# Decoder.net
KiCad netlist of a schematic drawn in EAGLE
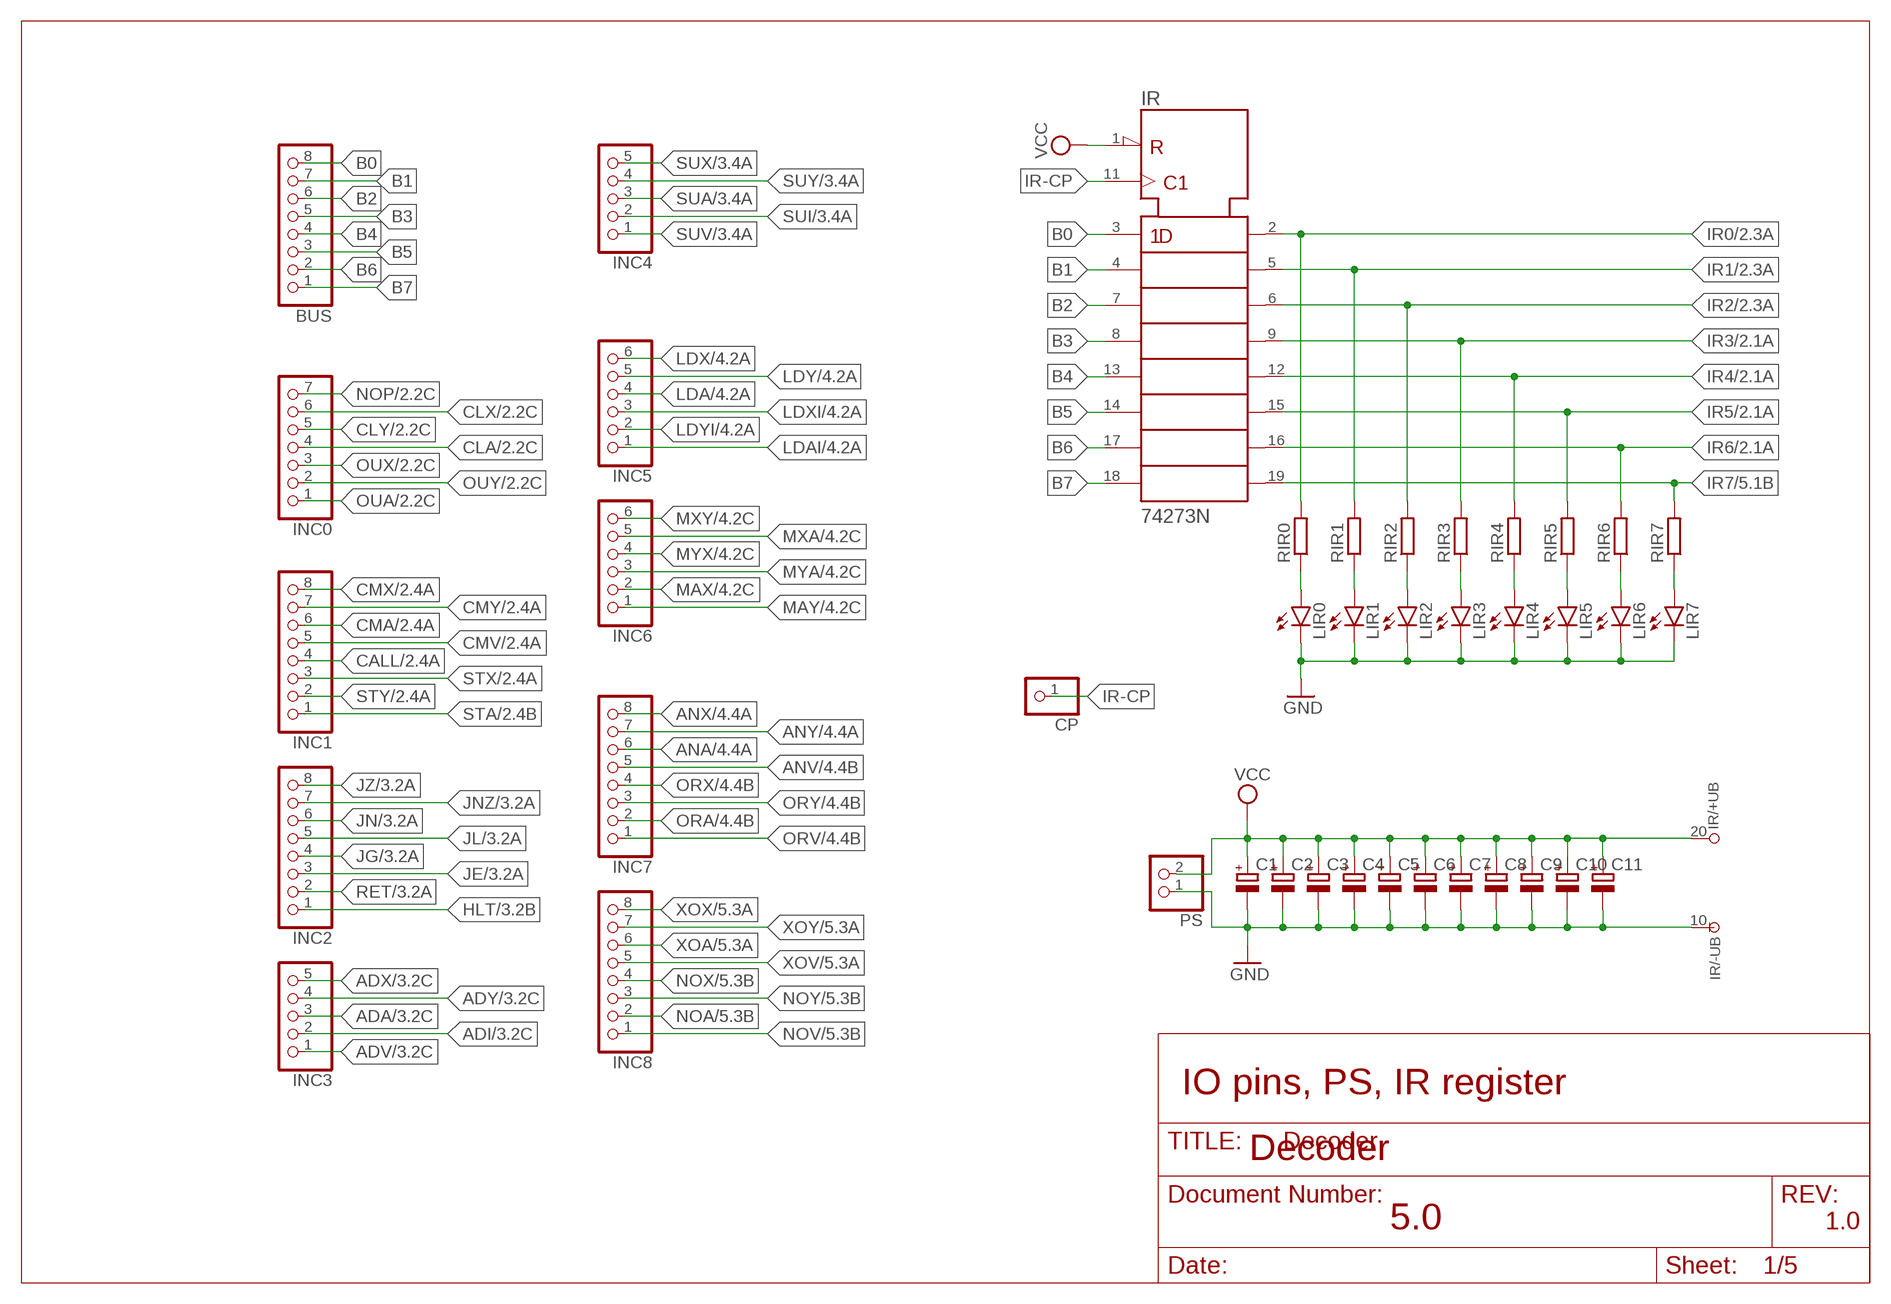
[diagram p0: schematic, sheet 1]
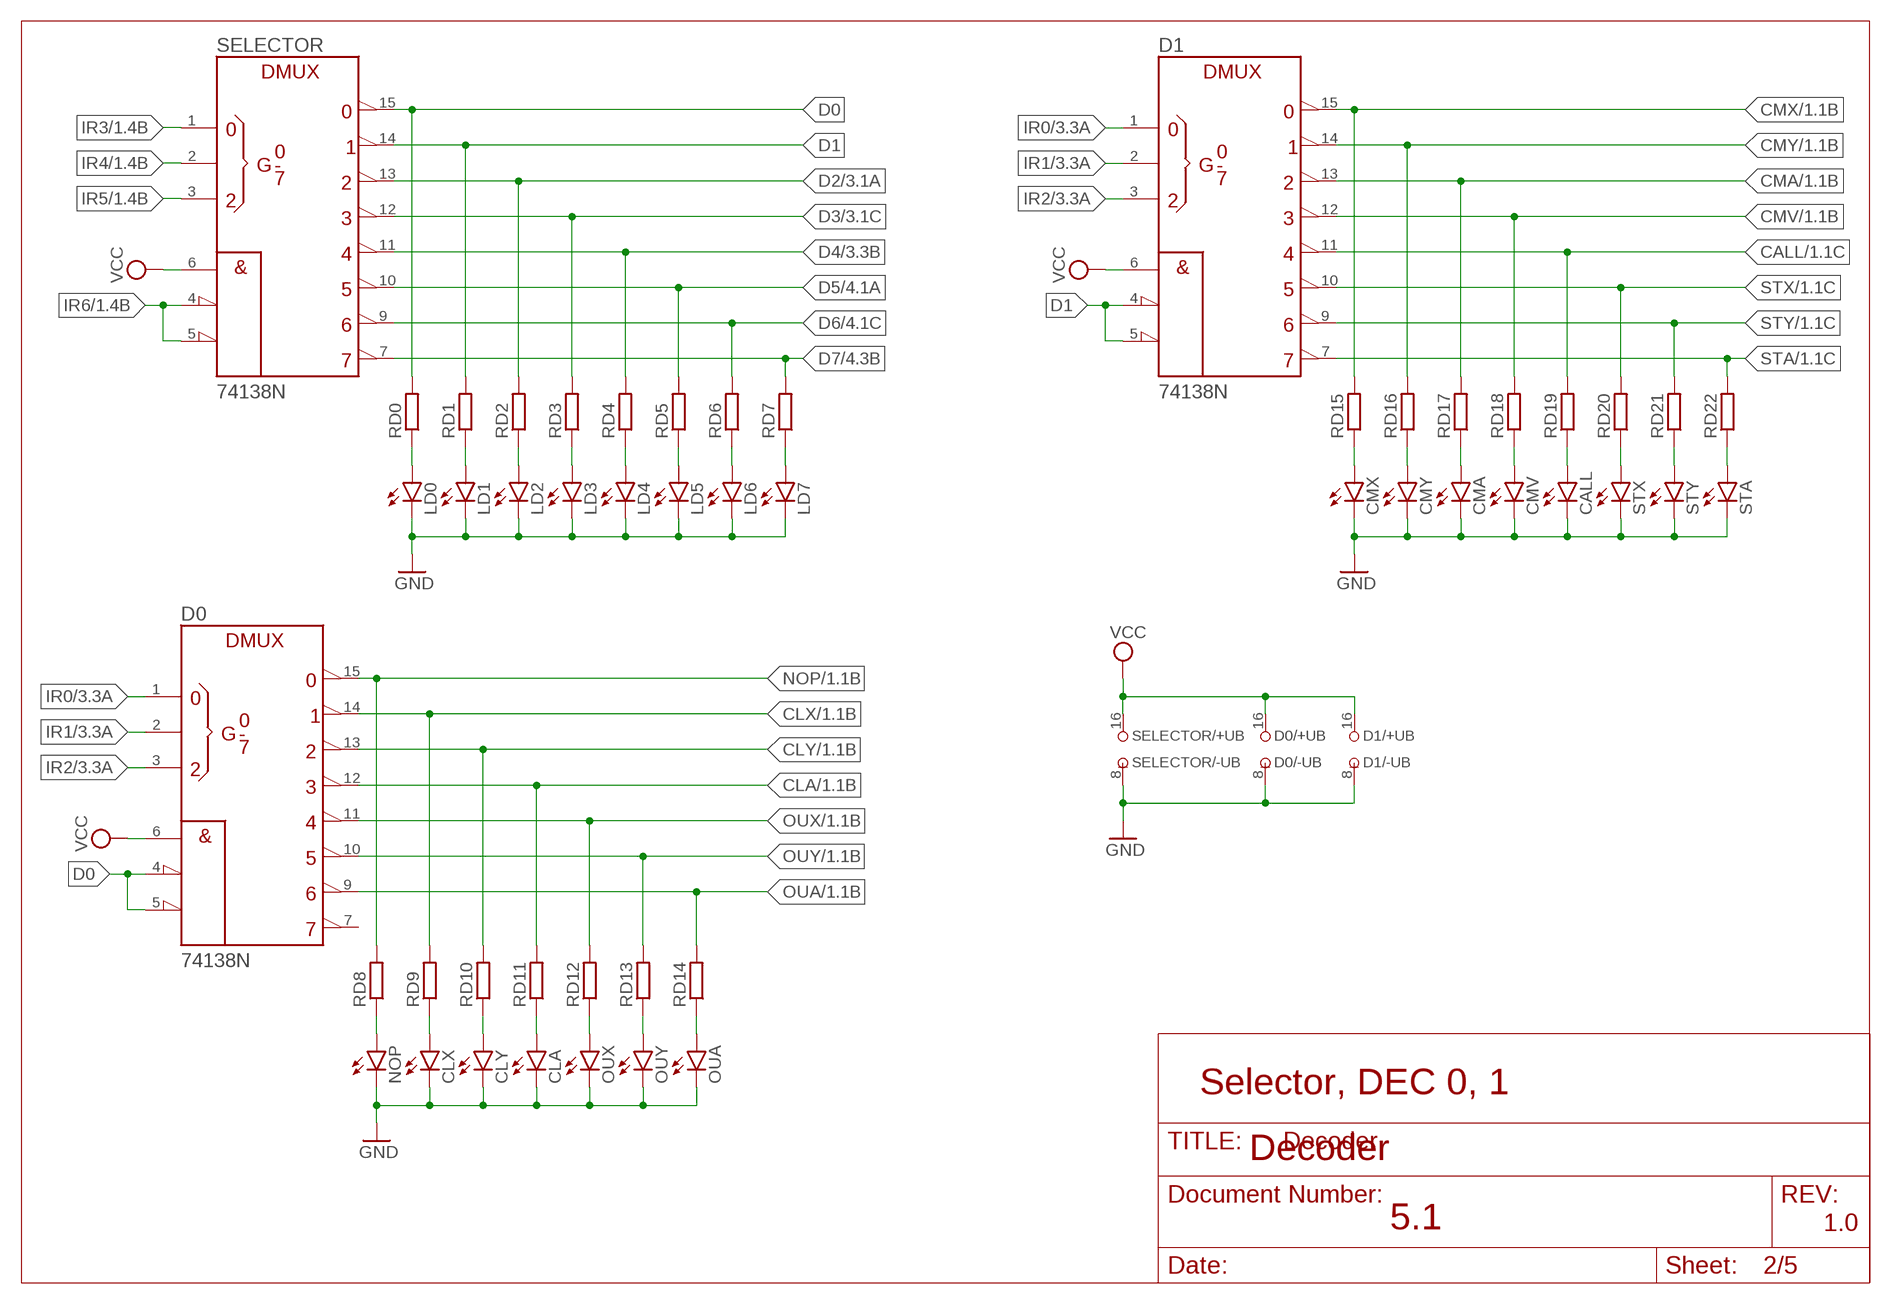
[diagram p1: schematic, sheet 2]
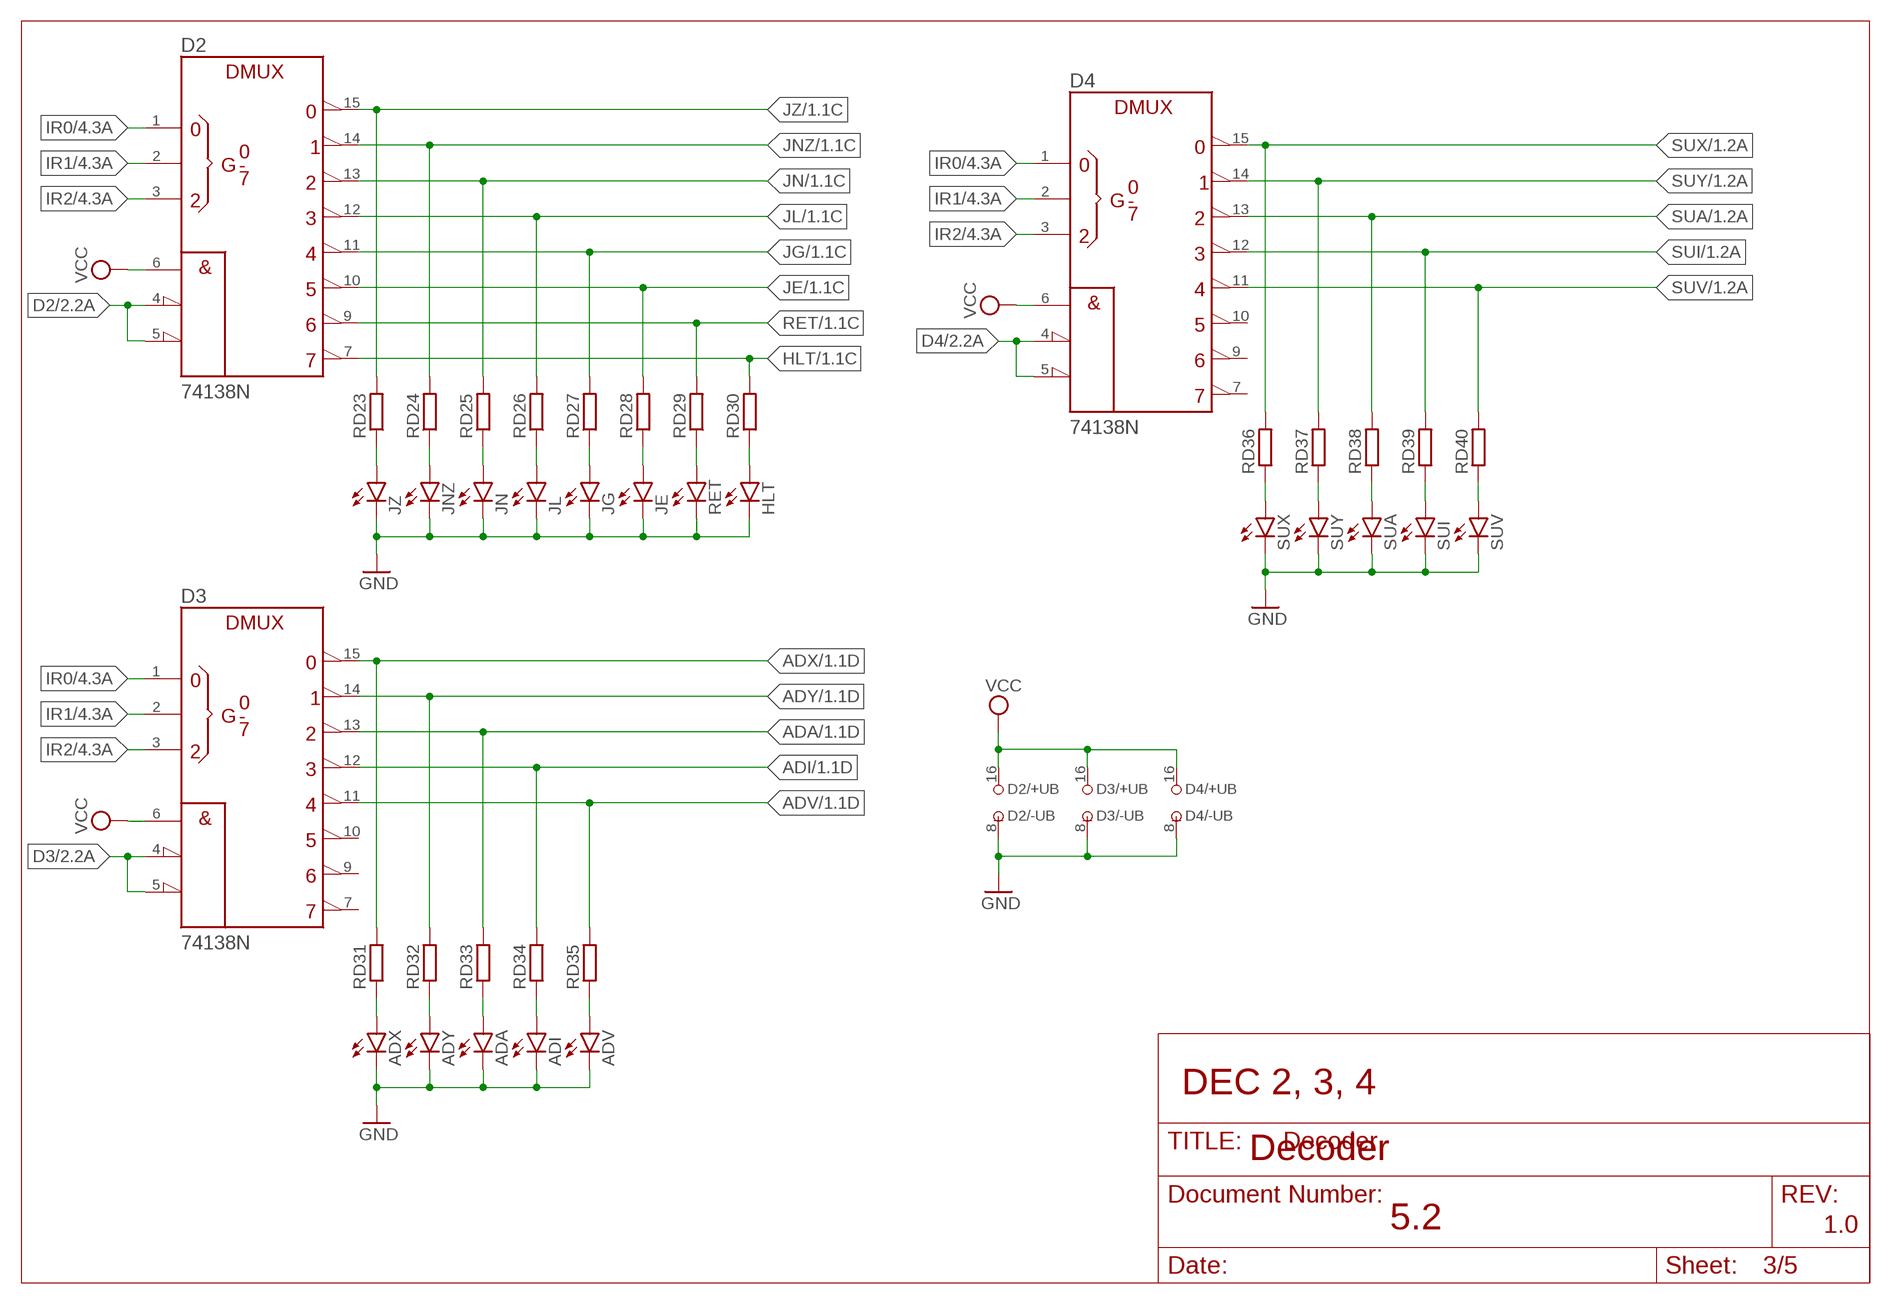
[diagram p2: schematic, sheet 3]
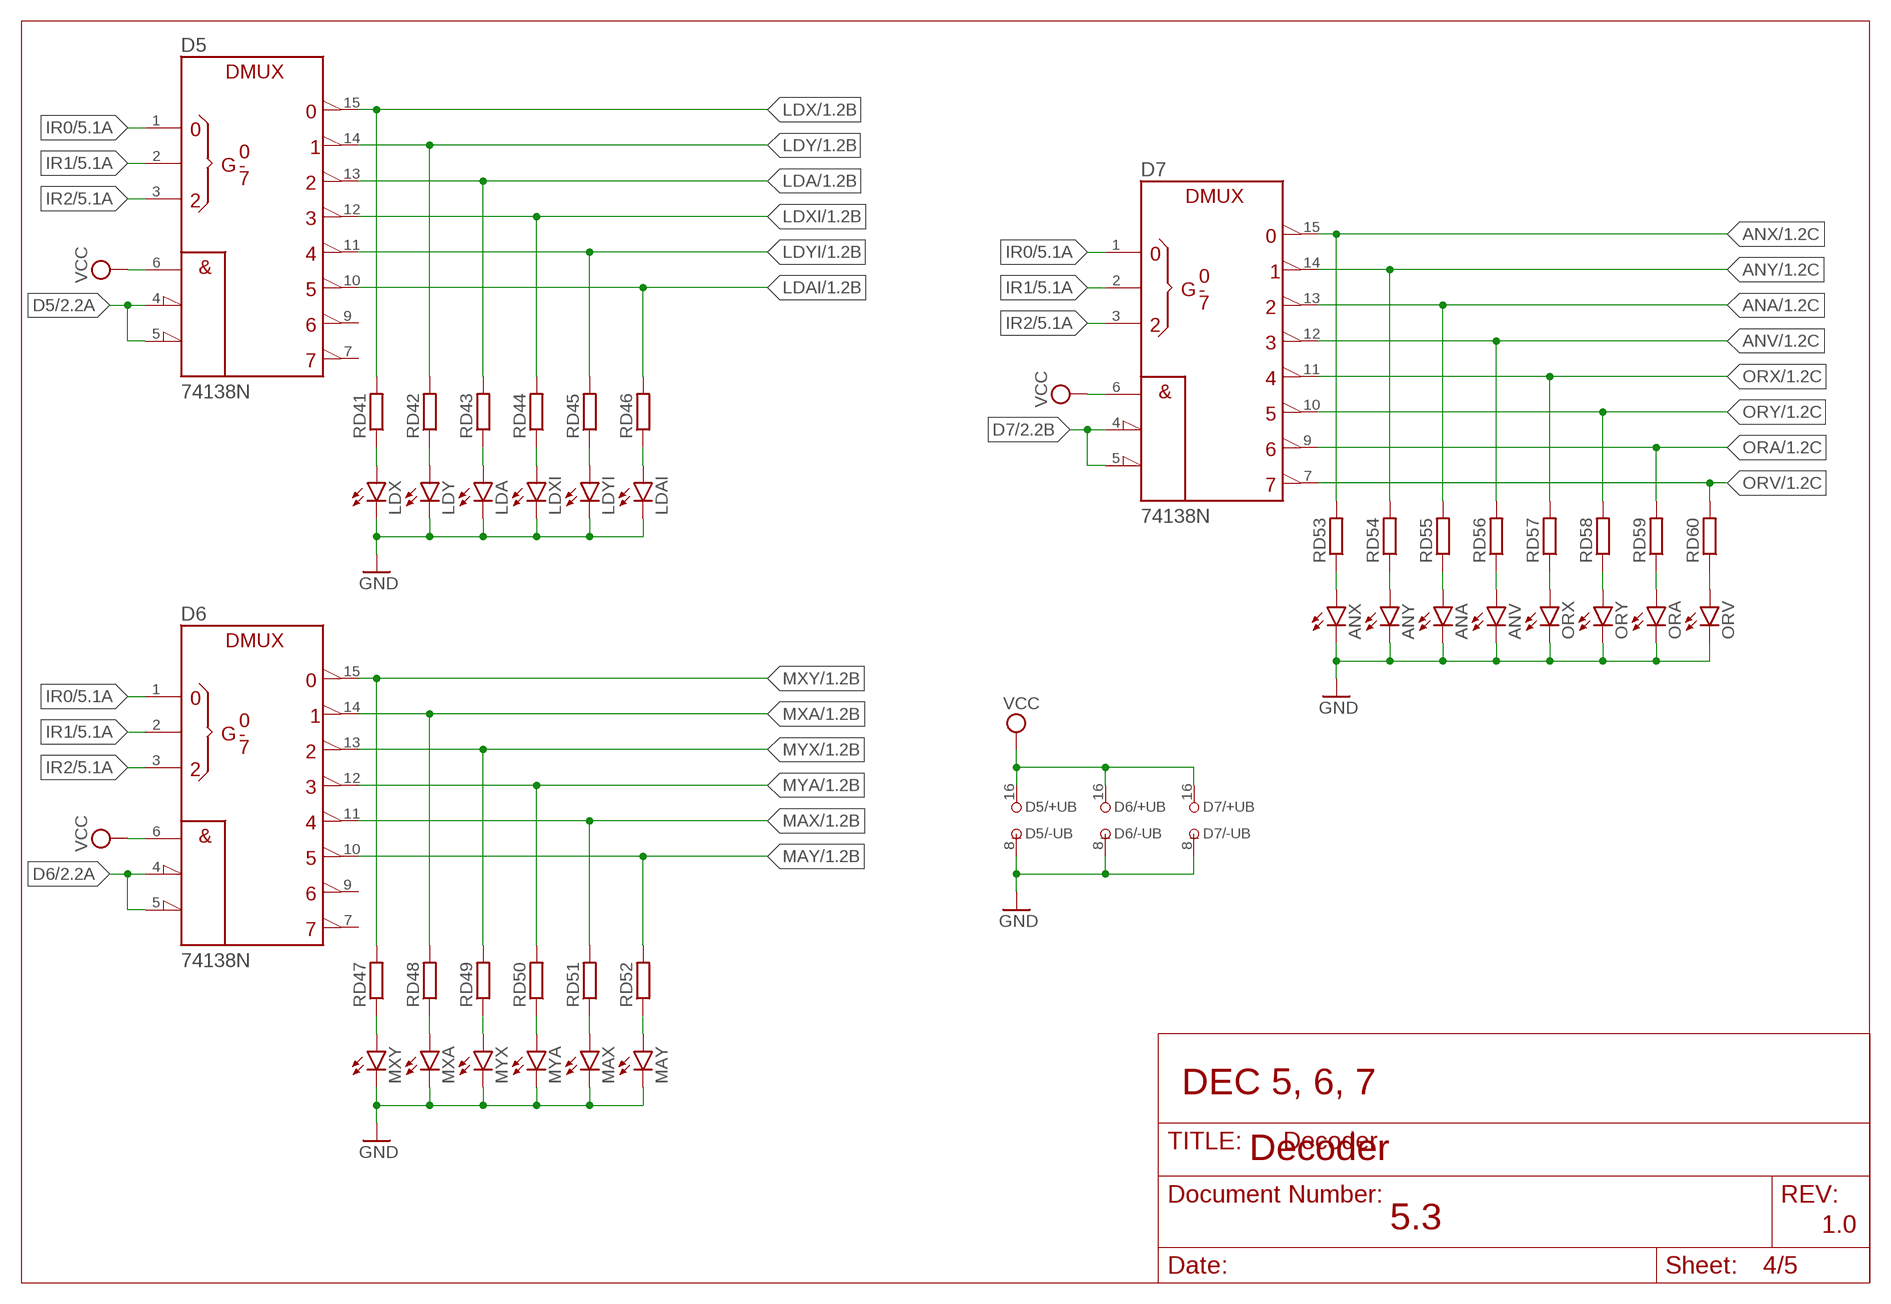
[diagram p3: schematic, sheet 4]
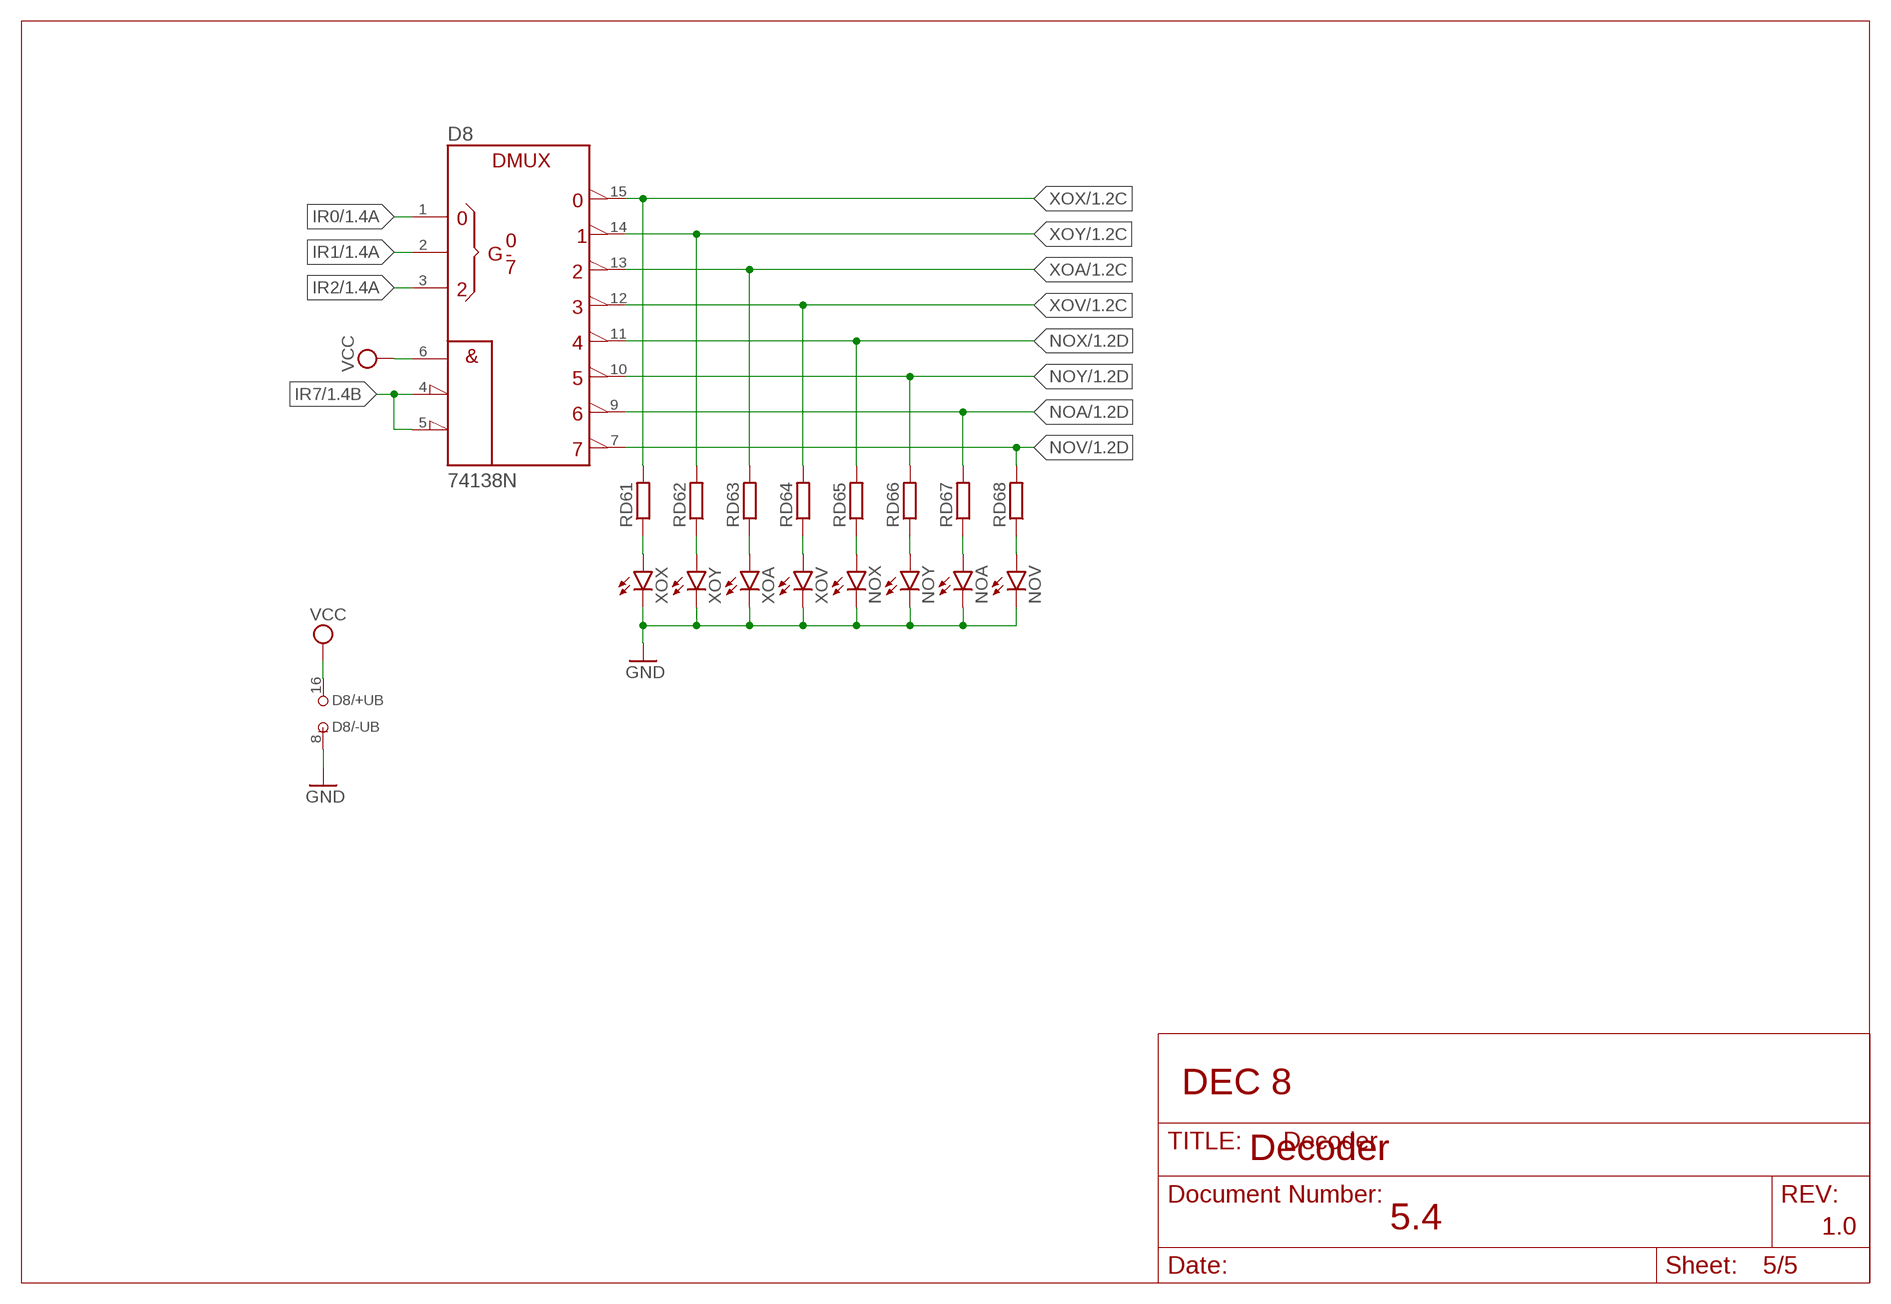
[diagram p4: schematic, sheet 5]

(export (version "E")
  (design (tool "Eeschema 10.0.6"))
  (components
    (comp (ref "CALL")
      (value "LED5MM")
      (footprint "eagle-import:LED5MM")
      (libsource (lib "eagle-import") (part "LED5MM"))
    )
    (comp (ref "CLA")
      (value "LED5MM")
      (footprint "eagle-import:LED5MM")
      (libsource (lib "eagle-import") (part "LED5MM"))
    )
    (comp (ref "CLX")
      (value "LED5MM")
      (footprint "eagle-import:LED5MM")
      (libsource (lib "eagle-import") (part "LED5MM"))
    )
    (comp (ref "CLY")
      (value "LED5MM")
      (footprint "eagle-import:LED5MM")
      (libsource (lib "eagle-import") (part "LED5MM"))
    )
    (comp (ref "CMA")
      (value "LED5MM")
      (footprint "eagle-import:LED5MM")
      (libsource (lib "eagle-import") (part "LED5MM"))
    )
    (comp (ref "CMV")
      (value "LED5MM")
      (footprint "eagle-import:LED5MM")
      (libsource (lib "eagle-import") (part "LED5MM"))
    )
    (comp (ref "CMX")
      (value "LED5MM")
      (footprint "eagle-import:LED5MM")
      (libsource (lib "eagle-import") (part "LED5MM"))
    )
    (comp (ref "CMY")
      (value "LED5MM")
      (footprint "eagle-import:LED5MM")
      (libsource (lib "eagle-import") (part "LED5MM"))
    )
    (comp (ref "D0")
      (value "74138N")
      (footprint "eagle-import:DIL16")
      (libsource (lib "eagle-import") (part "74138N"))
    )
    (comp (ref "D1")
      (value "74138N")
      (footprint "eagle-import:DIL16")
      (libsource (lib "eagle-import") (part "74138N"))
    )
    (comp (ref "LD0")
      (value "LED5MM")
      (footprint "eagle-import:LED5MM")
      (libsource (lib "eagle-import") (part "LED5MM"))
    )
    (comp (ref "LD1")
      (value "LED5MM")
      (footprint "eagle-import:LED5MM")
      (libsource (lib "eagle-import") (part "LED5MM"))
    )
    (comp (ref "LD2")
      (value "LED5MM")
      (footprint "eagle-import:LED5MM")
      (libsource (lib "eagle-import") (part "LED5MM"))
    )
    (comp (ref "LD3")
      (value "LED5MM")
      (footprint "eagle-import:LED5MM")
      (libsource (lib "eagle-import") (part "LED5MM"))
    )
    (comp (ref "LD4")
      (value "LED5MM")
      (footprint "eagle-import:LED5MM")
      (libsource (lib "eagle-import") (part "LED5MM"))
    )
    (comp (ref "LD5")
      (value "LED5MM")
      (footprint "eagle-import:LED5MM")
      (libsource (lib "eagle-import") (part "LED5MM"))
    )
    (comp (ref "LD6")
      (value "LED5MM")
      (footprint "eagle-import:LED5MM")
      (libsource (lib "eagle-import") (part "LED5MM"))
    )
    (comp (ref "LD7")
      (value "LED5MM")
      (footprint "eagle-import:LED5MM")
      (libsource (lib "eagle-import") (part "LED5MM"))
    )
    (comp (ref "NOP")
      (value "LED5MM")
      (footprint "eagle-import:LED5MM")
      (libsource (lib "eagle-import") (part "LED5MM"))
    )
    (comp (ref "OUA")
      (value "LED5MM")
      (footprint "eagle-import:LED5MM")
      (libsource (lib "eagle-import") (part "LED5MM"))
    )
    (comp (ref "OUX")
      (value "LED5MM")
      (footprint "eagle-import:LED5MM")
      (libsource (lib "eagle-import") (part "LED5MM"))
    )
    (comp (ref "OUY")
      (value "LED5MM")
      (footprint "eagle-import:LED5MM")
      (libsource (lib "eagle-import") (part "LED5MM"))
    )
    (comp (ref "RD0")
      (value "R-EU_0204/7")
      (footprint "eagle-import:0204_7")
      (libsource (lib "eagle-import") (part "R-EU_0204/7"))
    )
    (comp (ref "RD1")
      (value "R-EU_0204/7")
      (footprint "eagle-import:0204_7")
      (libsource (lib "eagle-import") (part "R-EU_0204/7"))
    )
    (comp (ref "RD2")
      (value "R-EU_0204/7")
      (footprint "eagle-import:0204_7")
      (libsource (lib "eagle-import") (part "R-EU_0204/7"))
    )
    (comp (ref "RD3")
      (value "R-EU_0204/7")
      (footprint "eagle-import:0204_7")
      (libsource (lib "eagle-import") (part "R-EU_0204/7"))
    )
    (comp (ref "RD4")
      (value "R-EU_0204/7")
      (footprint "eagle-import:0204_7")
      (libsource (lib "eagle-import") (part "R-EU_0204/7"))
    )
    (comp (ref "RD5")
      (value "R-EU_0204/7")
      (footprint "eagle-import:0204_7")
      (libsource (lib "eagle-import") (part "R-EU_0204/7"))
    )
    (comp (ref "RD6")
      (value "R-EU_0204/7")
      (footprint "eagle-import:0204_7")
      (libsource (lib "eagle-import") (part "R-EU_0204/7"))
    )
    (comp (ref "RD7")
      (value "R-EU_0204/7")
      (footprint "eagle-import:0204_7")
      (libsource (lib "eagle-import") (part "R-EU_0204/7"))
    )
    (comp (ref "RD8")
      (value "R-EU_0204/7")
      (footprint "eagle-import:0204_7")
      (libsource (lib "eagle-import") (part "R-EU_0204/7"))
    )
    (comp (ref "RD9")
      (value "R-EU_0204/7")
      (footprint "eagle-import:0204_7")
      (libsource (lib "eagle-import") (part "R-EU_0204/7"))
    )
    (comp (ref "RD10")
      (value "R-EU_0204/7")
      (footprint "eagle-import:0204_7")
      (libsource (lib "eagle-import") (part "R-EU_0204/7"))
    )
    (comp (ref "RD11")
      (value "R-EU_0204/7")
      (footprint "eagle-import:0204_7")
      (libsource (lib "eagle-import") (part "R-EU_0204/7"))
    )
    (comp (ref "RD12")
      (value "R-EU_0204/7")
      (footprint "eagle-import:0204_7")
      (libsource (lib "eagle-import") (part "R-EU_0204/7"))
    )
    (comp (ref "RD13")
      (value "R-EU_0204/7")
      (footprint "eagle-import:0204_7")
      (libsource (lib "eagle-import") (part "R-EU_0204/7"))
    )
    (comp (ref "RD14")
      (value "R-EU_0204/7")
      (footprint "eagle-import:0204_7")
      (libsource (lib "eagle-import") (part "R-EU_0204/7"))
    )
    (comp (ref "RD15")
      (value "R-EU_0204/7")
      (footprint "eagle-import:0204_7")
      (libsource (lib "eagle-import") (part "R-EU_0204/7"))
    )
    (comp (ref "RD16")
      (value "R-EU_0204/7")
      (footprint "eagle-import:0204_7")
      (libsource (lib "eagle-import") (part "R-EU_0204/7"))
    )
    (comp (ref "RD17")
      (value "R-EU_0204/7")
      (footprint "eagle-import:0204_7")
      (libsource (lib "eagle-import") (part "R-EU_0204/7"))
    )
    (comp (ref "RD18")
      (value "R-EU_0204/7")
      (footprint "eagle-import:0204_7")
      (libsource (lib "eagle-import") (part "R-EU_0204/7"))
    )
    (comp (ref "RD19")
      (value "R-EU_0204/7")
      (footprint "eagle-import:0204_7")
      (libsource (lib "eagle-import") (part "R-EU_0204/7"))
    )
    (comp (ref "RD20")
      (value "R-EU_0204/7")
      (footprint "eagle-import:0204_7")
      (libsource (lib "eagle-import") (part "R-EU_0204/7"))
    )
    (comp (ref "RD21")
      (value "R-EU_0204/7")
      (footprint "eagle-import:0204_7")
      (libsource (lib "eagle-import") (part "R-EU_0204/7"))
    )
    (comp (ref "RD22")
      (value "R-EU_0204/7")
      (footprint "eagle-import:0204_7")
      (libsource (lib "eagle-import") (part "R-EU_0204/7"))
    )
    (comp (ref "SELECTOR")
      (value "74138N")
      (footprint "eagle-import:DIL16")
      (libsource (lib "eagle-import") (part "74138N"))
    )
    (comp (ref "STA")
      (value "LED5MM")
      (footprint "eagle-import:LED5MM")
      (libsource (lib "eagle-import") (part "LED5MM"))
    )
    (comp (ref "STX")
      (value "LED5MM")
      (footprint "eagle-import:LED5MM")
      (libsource (lib "eagle-import") (part "LED5MM"))
    )
    (comp (ref "STY")
      (value "LED5MM")
      (footprint "eagle-import:LED5MM")
      (libsource (lib "eagle-import") (part "LED5MM"))
    )
    (comp (ref "ANA")
      (value "LED5MM")
      (footprint "eagle-import:LED5MM")
      (libsource (lib "eagle-import") (part "LED5MM"))
    )
    (comp (ref "ANV")
      (value "LED5MM")
      (footprint "eagle-import:LED5MM")
      (libsource (lib "eagle-import") (part "LED5MM"))
    )
    (comp (ref "ANX")
      (value "LED5MM")
      (footprint "eagle-import:LED5MM")
      (libsource (lib "eagle-import") (part "LED5MM"))
    )
    (comp (ref "ANY")
      (value "LED5MM")
      (footprint "eagle-import:LED5MM")
      (libsource (lib "eagle-import") (part "LED5MM"))
    )
    (comp (ref "D5")
      (value "74138N")
      (footprint "eagle-import:DIL16")
      (libsource (lib "eagle-import") (part "74138N"))
    )
    (comp (ref "D6")
      (value "74138N")
      (footprint "eagle-import:DIL16")
      (libsource (lib "eagle-import") (part "74138N"))
    )
    (comp (ref "D7")
      (value "74138N")
      (footprint "eagle-import:DIL16")
      (libsource (lib "eagle-import") (part "74138N"))
    )
    (comp (ref "LDA")
      (value "LED5MM")
      (footprint "eagle-import:LED5MM")
      (libsource (lib "eagle-import") (part "LED5MM"))
    )
    (comp (ref "LDAI")
      (value "LED5MM")
      (footprint "eagle-import:LED5MM")
      (libsource (lib "eagle-import") (part "LED5MM"))
    )
    (comp (ref "LDX")
      (value "LED5MM")
      (footprint "eagle-import:LED5MM")
      (libsource (lib "eagle-import") (part "LED5MM"))
    )
    (comp (ref "LDXI")
      (value "LED5MM")
      (footprint "eagle-import:LED5MM")
      (libsource (lib "eagle-import") (part "LED5MM"))
    )
    (comp (ref "LDY")
      (value "LED5MM")
      (footprint "eagle-import:LED5MM")
      (libsource (lib "eagle-import") (part "LED5MM"))
    )
    (comp (ref "LDYI")
      (value "LED5MM")
      (footprint "eagle-import:LED5MM")
      (libsource (lib "eagle-import") (part "LED5MM"))
    )
    (comp (ref "MAX")
      (value "LED5MM")
      (footprint "eagle-import:LED5MM")
      (libsource (lib "eagle-import") (part "LED5MM"))
    )
    (comp (ref "MAY")
      (value "LED5MM")
      (footprint "eagle-import:LED5MM")
      (libsource (lib "eagle-import") (part "LED5MM"))
    )
    (comp (ref "MXA")
      (value "LED5MM")
      (footprint "eagle-import:LED5MM")
      (libsource (lib "eagle-import") (part "LED5MM"))
    )
    (comp (ref "MXY")
      (value "LED5MM")
      (footprint "eagle-import:LED5MM")
      (libsource (lib "eagle-import") (part "LED5MM"))
    )
    (comp (ref "MYA")
      (value "LED5MM")
      (footprint "eagle-import:LED5MM")
      (libsource (lib "eagle-import") (part "LED5MM"))
    )
    (comp (ref "MYX")
      (value "LED5MM")
      (footprint "eagle-import:LED5MM")
      (libsource (lib "eagle-import") (part "LED5MM"))
    )
    (comp (ref "ORA")
      (value "LED5MM")
      (footprint "eagle-import:LED5MM")
      (libsource (lib "eagle-import") (part "LED5MM"))
    )
    (comp (ref "ORV")
      (value "LED5MM")
      (footprint "eagle-import:LED5MM")
      (libsource (lib "eagle-import") (part "LED5MM"))
    )
    (comp (ref "ORX")
      (value "LED5MM")
      (footprint "eagle-import:LED5MM")
      (libsource (lib "eagle-import") (part "LED5MM"))
    )
    (comp (ref "ORY")
      (value "LED5MM")
      (footprint "eagle-import:LED5MM")
      (libsource (lib "eagle-import") (part "LED5MM"))
    )
    (comp (ref "RD41")
      (value "R-EU_0204/7")
      (footprint "eagle-import:0204_7")
      (libsource (lib "eagle-import") (part "R-EU_0204/7"))
    )
    (comp (ref "RD42")
      (value "R-EU_0204/7")
      (footprint "eagle-import:0204_7")
      (libsource (lib "eagle-import") (part "R-EU_0204/7"))
    )
    (comp (ref "RD43")
      (value "R-EU_0204/7")
      (footprint "eagle-import:0204_7")
      (libsource (lib "eagle-import") (part "R-EU_0204/7"))
    )
    (comp (ref "RD44")
      (value "R-EU_0204/7")
      (footprint "eagle-import:0204_7")
      (libsource (lib "eagle-import") (part "R-EU_0204/7"))
    )
    (comp (ref "RD45")
      (value "R-EU_0204/7")
      (footprint "eagle-import:0204_7")
      (libsource (lib "eagle-import") (part "R-EU_0204/7"))
    )
    (comp (ref "RD46")
      (value "R-EU_0204/7")
      (footprint "eagle-import:0204_7")
      (libsource (lib "eagle-import") (part "R-EU_0204/7"))
    )
    (comp (ref "RD47")
      (value "R-EU_0204/7")
      (footprint "eagle-import:0204_7")
      (libsource (lib "eagle-import") (part "R-EU_0204/7"))
    )
    (comp (ref "RD48")
      (value "R-EU_0204/7")
      (footprint "eagle-import:0204_7")
      (libsource (lib "eagle-import") (part "R-EU_0204/7"))
    )
    (comp (ref "RD49")
      (value "R-EU_0204/7")
      (footprint "eagle-import:0204_7")
      (libsource (lib "eagle-import") (part "R-EU_0204/7"))
    )
    (comp (ref "RD50")
      (value "R-EU_0204/7")
      (footprint "eagle-import:0204_7")
      (libsource (lib "eagle-import") (part "R-EU_0204/7"))
    )
    (comp (ref "RD51")
      (value "R-EU_0204/7")
      (footprint "eagle-import:0204_7")
      (libsource (lib "eagle-import") (part "R-EU_0204/7"))
    )
    (comp (ref "RD52")
      (value "R-EU_0204/7")
      (footprint "eagle-import:0204_7")
      (libsource (lib "eagle-import") (part "R-EU_0204/7"))
    )
    (comp (ref "RD53")
      (value "R-EU_0204/7")
      (footprint "eagle-import:0204_7")
      (libsource (lib "eagle-import") (part "R-EU_0204/7"))
    )
    (comp (ref "RD54")
      (value "R-EU_0204/7")
      (footprint "eagle-import:0204_7")
      (libsource (lib "eagle-import") (part "R-EU_0204/7"))
    )
    (comp (ref "RD55")
      (value "R-EU_0204/7")
      (footprint "eagle-import:0204_7")
      (libsource (lib "eagle-import") (part "R-EU_0204/7"))
    )
    (comp (ref "RD56")
      (value "R-EU_0204/7")
      (footprint "eagle-import:0204_7")
      (libsource (lib "eagle-import") (part "R-EU_0204/7"))
    )
    (comp (ref "RD57")
      (value "R-EU_0204/7")
      (footprint "eagle-import:0204_7")
      (libsource (lib "eagle-import") (part "R-EU_0204/7"))
    )
    (comp (ref "RD58")
      (value "R-EU_0204/7")
      (footprint "eagle-import:0204_7")
      (libsource (lib "eagle-import") (part "R-EU_0204/7"))
    )
    (comp (ref "RD59")
      (value "R-EU_0204/7")
      (footprint "eagle-import:0204_7")
      (libsource (lib "eagle-import") (part "R-EU_0204/7"))
    )
    (comp (ref "RD60")
      (value "R-EU_0204/7")
      (footprint "eagle-import:0204_7")
      (libsource (lib "eagle-import") (part "R-EU_0204/7"))
    )
    (comp (ref "ADA")
      (value "LED5MM")
      (footprint "eagle-import:LED5MM")
      (libsource (lib "eagle-import") (part "LED5MM"))
    )
    (comp (ref "ADI")
      (value "LED5MM")
      (footprint "eagle-import:LED5MM")
      (libsource (lib "eagle-import") (part "LED5MM"))
    )
    (comp (ref "ADV")
      (value "LED5MM")
      (footprint "eagle-import:LED5MM")
      (libsource (lib "eagle-import") (part "LED5MM"))
    )
    (comp (ref "ADX")
      (value "LED5MM")
      (footprint "eagle-import:LED5MM")
      (libsource (lib "eagle-import") (part "LED5MM"))
    )
    (comp (ref "ADY")
      (value "LED5MM")
      (footprint "eagle-import:LED5MM")
      (libsource (lib "eagle-import") (part "LED5MM"))
    )
    (comp (ref "D2")
      (value "74138N")
      (footprint "eagle-import:DIL16")
      (libsource (lib "eagle-import") (part "74138N"))
    )
    (comp (ref "D3")
      (value "74138N")
      (footprint "eagle-import:DIL16")
      (libsource (lib "eagle-import") (part "74138N"))
    )
    (comp (ref "D4")
      (value "74138N")
      (footprint "eagle-import:DIL16")
      (libsource (lib "eagle-import") (part "74138N"))
    )
    (comp (ref "HLT")
      (value "LED5MM")
      (footprint "eagle-import:LED5MM")
      (libsource (lib "eagle-import") (part "LED5MM"))
    )
    (comp (ref "JE")
      (value "LED5MM")
      (footprint "eagle-import:LED5MM")
      (libsource (lib "eagle-import") (part "LED5MM"))
    )
    (comp (ref "JG")
      (value "LED5MM")
      (footprint "eagle-import:LED5MM")
      (libsource (lib "eagle-import") (part "LED5MM"))
    )
    (comp (ref "JL")
      (value "LED5MM")
      (footprint "eagle-import:LED5MM")
      (libsource (lib "eagle-import") (part "LED5MM"))
    )
    (comp (ref "JN")
      (value "LED5MM")
      (footprint "eagle-import:LED5MM")
      (libsource (lib "eagle-import") (part "LED5MM"))
    )
    (comp (ref "JNZ")
      (value "LED5MM")
      (footprint "eagle-import:LED5MM")
      (libsource (lib "eagle-import") (part "LED5MM"))
    )
    (comp (ref "JZ")
      (value "LED5MM")
      (footprint "eagle-import:LED5MM")
      (libsource (lib "eagle-import") (part "LED5MM"))
    )
    (comp (ref "RD23")
      (value "R-EU_0204/7")
      (footprint "eagle-import:0204_7")
      (libsource (lib "eagle-import") (part "R-EU_0204/7"))
    )
    (comp (ref "RD24")
      (value "R-EU_0204/7")
      (footprint "eagle-import:0204_7")
      (libsource (lib "eagle-import") (part "R-EU_0204/7"))
    )
    (comp (ref "RD25")
      (value "R-EU_0204/7")
      (footprint "eagle-import:0204_7")
      (libsource (lib "eagle-import") (part "R-EU_0204/7"))
    )
    (comp (ref "RD26")
      (value "R-EU_0204/7")
      (footprint "eagle-import:0204_7")
      (libsource (lib "eagle-import") (part "R-EU_0204/7"))
    )
    (comp (ref "RD27")
      (value "R-EU_0204/7")
      (footprint "eagle-import:0204_7")
      (libsource (lib "eagle-import") (part "R-EU_0204/7"))
    )
    (comp (ref "RD28")
      (value "R-EU_0204/7")
      (footprint "eagle-import:0204_7")
      (libsource (lib "eagle-import") (part "R-EU_0204/7"))
    )
    (comp (ref "RD29")
      (value "R-EU_0204/7")
      (footprint "eagle-import:0204_7")
      (libsource (lib "eagle-import") (part "R-EU_0204/7"))
    )
    (comp (ref "RD30")
      (value "R-EU_0204/7")
      (footprint "eagle-import:0204_7")
      (libsource (lib "eagle-import") (part "R-EU_0204/7"))
    )
    (comp (ref "RD31")
      (value "R-EU_0204/7")
      (footprint "eagle-import:0204_7")
      (libsource (lib "eagle-import") (part "R-EU_0204/7"))
    )
    (comp (ref "RD32")
      (value "R-EU_0204/7")
      (footprint "eagle-import:0204_7")
      (libsource (lib "eagle-import") (part "R-EU_0204/7"))
    )
    (comp (ref "RD33")
      (value "R-EU_0204/7")
      (footprint "eagle-import:0204_7")
      (libsource (lib "eagle-import") (part "R-EU_0204/7"))
    )
    (comp (ref "RD34")
      (value "R-EU_0204/7")
      (footprint "eagle-import:0204_7")
      (libsource (lib "eagle-import") (part "R-EU_0204/7"))
    )
    (comp (ref "RD35")
      (value "R-EU_0204/7")
      (footprint "eagle-import:0204_7")
      (libsource (lib "eagle-import") (part "R-EU_0204/7"))
    )
    (comp (ref "RD36")
      (value "R-EU_0204/7")
      (footprint "eagle-import:0204_7")
      (libsource (lib "eagle-import") (part "R-EU_0204/7"))
    )
    (comp (ref "RD37")
      (value "R-EU_0204/7")
      (footprint "eagle-import:0204_7")
      (libsource (lib "eagle-import") (part "R-EU_0204/7"))
    )
    (comp (ref "RD38")
      (value "R-EU_0204/7")
      (footprint "eagle-import:0204_7")
      (libsource (lib "eagle-import") (part "R-EU_0204/7"))
    )
    (comp (ref "RD39")
      (value "R-EU_0204/7")
      (footprint "eagle-import:0204_7")
      (libsource (lib "eagle-import") (part "R-EU_0204/7"))
    )
    (comp (ref "RD40")
      (value "R-EU_0204/7")
      (footprint "eagle-import:0204_7")
      (libsource (lib "eagle-import") (part "R-EU_0204/7"))
    )
    (comp (ref "RET")
      (value "LED5MM")
      (footprint "eagle-import:LED5MM")
      (libsource (lib "eagle-import") (part "LED5MM"))
    )
    (comp (ref "SUA")
      (value "LED5MM")
      (footprint "eagle-import:LED5MM")
      (libsource (lib "eagle-import") (part "LED5MM"))
    )
    (comp (ref "SUI")
      (value "LED5MM")
      (footprint "eagle-import:LED5MM")
      (libsource (lib "eagle-import") (part "LED5MM"))
    )
    (comp (ref "SUV")
      (value "LED5MM")
      (footprint "eagle-import:LED5MM")
      (libsource (lib "eagle-import") (part "LED5MM"))
    )
    (comp (ref "SUX")
      (value "LED5MM")
      (footprint "eagle-import:LED5MM")
      (libsource (lib "eagle-import") (part "LED5MM"))
    )
    (comp (ref "SUY")
      (value "LED5MM")
      (footprint "eagle-import:LED5MM")
      (libsource (lib "eagle-import") (part "LED5MM"))
    )
    (comp (ref "BUS")
      (value "PINHD-1X8")
      (footprint "eagle-import:1X08")
      (libsource (lib "eagle-import") (part "PINHD-1X8"))
    )
    (comp (ref "C1")
      (value "CPOL-EUE2.5-6")
      (footprint "eagle-import:E2,5-6")
      (libsource (lib "eagle-import") (part "CPOL-EUE2.5-6"))
    )
    (comp (ref "C2")
      (value "CPOL-EUE2.5-6")
      (footprint "eagle-import:E2,5-6")
      (libsource (lib "eagle-import") (part "CPOL-EUE2.5-6"))
    )
    (comp (ref "C3")
      (value "CPOL-EUE2.5-6")
      (footprint "eagle-import:E2,5-6")
      (libsource (lib "eagle-import") (part "CPOL-EUE2.5-6"))
    )
    (comp (ref "C4")
      (value "CPOL-EUE2.5-6")
      (footprint "eagle-import:E2,5-6")
      (libsource (lib "eagle-import") (part "CPOL-EUE2.5-6"))
    )
    (comp (ref "C5")
      (value "CPOL-EUE2.5-6")
      (footprint "eagle-import:E2,5-6")
      (libsource (lib "eagle-import") (part "CPOL-EUE2.5-6"))
    )
    (comp (ref "C6")
      (value "CPOL-EUE2.5-6")
      (footprint "eagle-import:E2,5-6")
      (libsource (lib "eagle-import") (part "CPOL-EUE2.5-6"))
    )
    (comp (ref "C7")
      (value "CPOL-EUE2.5-6")
      (footprint "eagle-import:E2,5-6")
      (libsource (lib "eagle-import") (part "CPOL-EUE2.5-6"))
    )
    (comp (ref "C8")
      (value "CPOL-EUE2.5-6")
      (footprint "eagle-import:E2,5-6")
      (libsource (lib "eagle-import") (part "CPOL-EUE2.5-6"))
    )
    (comp (ref "C9")
      (value "CPOL-EUE2.5-6")
      (footprint "eagle-import:E2,5-6")
      (libsource (lib "eagle-import") (part "CPOL-EUE2.5-6"))
    )
    (comp (ref "C10")
      (value "CPOL-EUE2.5-6")
      (footprint "eagle-import:E2,5-6")
      (libsource (lib "eagle-import") (part "CPOL-EUE2.5-6"))
    )
    (comp (ref "C11")
      (value "CPOL-EUE2.5-6")
      (footprint "eagle-import:E2,5-6")
      (libsource (lib "eagle-import") (part "CPOL-EUE2.5-6"))
    )
    (comp (ref "CP")
      (value "PINHD-1X1")
      (footprint "eagle-import:1X01")
      (libsource (lib "eagle-import") (part "PINHD-1X1"))
    )
    (comp (ref "INC0")
      (value "PINHD-1X7")
      (footprint "eagle-import:1X07")
      (libsource (lib "eagle-import") (part "PINHD-1X7"))
    )
    (comp (ref "INC1")
      (value "PINHD-1X8")
      (footprint "eagle-import:1X08")
      (libsource (lib "eagle-import") (part "PINHD-1X8"))
    )
    (comp (ref "INC2")
      (value "PINHD-1X8")
      (footprint "eagle-import:1X08")
      (libsource (lib "eagle-import") (part "PINHD-1X8"))
    )
    (comp (ref "INC3")
      (value "PINHD-1X5")
      (footprint "eagle-import:1X05")
      (libsource (lib "eagle-import") (part "PINHD-1X5"))
    )
    (comp (ref "INC4")
      (value "PINHD-1X5")
      (footprint "eagle-import:1X05")
      (libsource (lib "eagle-import") (part "PINHD-1X5"))
    )
    (comp (ref "INC5")
      (value "PINHD-1X6")
      (footprint "eagle-import:1X06")
      (libsource (lib "eagle-import") (part "PINHD-1X6"))
    )
    (comp (ref "INC6")
      (value "PINHD-1X6")
      (footprint "eagle-import:1X06")
      (libsource (lib "eagle-import") (part "PINHD-1X6"))
    )
    (comp (ref "INC7")
      (value "PINHD-1X8")
      (footprint "eagle-import:1X08")
      (libsource (lib "eagle-import") (part "PINHD-1X8"))
    )
    (comp (ref "INC8")
      (value "PINHD-1X8")
      (footprint "eagle-import:1X08")
      (libsource (lib "eagle-import") (part "PINHD-1X8"))
    )
    (comp (ref "IR")
      (value "74273N")
      (footprint "eagle-import:DIL20")
      (libsource (lib "eagle-import") (part "74273N"))
    )
    (comp (ref "LIR0")
      (value "LED5MM")
      (footprint "eagle-import:LED5MM")
      (libsource (lib "eagle-import") (part "LED5MM"))
    )
    (comp (ref "LIR1")
      (value "LED5MM")
      (footprint "eagle-import:LED5MM")
      (libsource (lib "eagle-import") (part "LED5MM"))
    )
    (comp (ref "LIR2")
      (value "LED5MM")
      (footprint "eagle-import:LED5MM")
      (libsource (lib "eagle-import") (part "LED5MM"))
    )
    (comp (ref "LIR3")
      (value "LED5MM")
      (footprint "eagle-import:LED5MM")
      (libsource (lib "eagle-import") (part "LED5MM"))
    )
    (comp (ref "LIR4")
      (value "LED5MM")
      (footprint "eagle-import:LED5MM")
      (libsource (lib "eagle-import") (part "LED5MM"))
    )
    (comp (ref "LIR5")
      (value "LED5MM")
      (footprint "eagle-import:LED5MM")
      (libsource (lib "eagle-import") (part "LED5MM"))
    )
    (comp (ref "LIR6")
      (value "LED5MM")
      (footprint "eagle-import:LED5MM")
      (libsource (lib "eagle-import") (part "LED5MM"))
    )
    (comp (ref "LIR7")
      (value "LED5MM")
      (footprint "eagle-import:LED5MM")
      (libsource (lib "eagle-import") (part "LED5MM"))
    )
    (comp (ref "PS")
      (value "PINHD-1X2")
      (footprint "eagle-import:1X02")
      (libsource (lib "eagle-import") (part "PINHD-1X2"))
    )
    (comp (ref "RIR0")
      (value "R-EU_0204/7")
      (footprint "eagle-import:0204_7")
      (libsource (lib "eagle-import") (part "R-EU_0204/7"))
    )
    (comp (ref "RIR1")
      (value "R-EU_0204/7")
      (footprint "eagle-import:0204_7")
      (libsource (lib "eagle-import") (part "R-EU_0204/7"))
    )
    (comp (ref "RIR2")
      (value "R-EU_0204/7")
      (footprint "eagle-import:0204_7")
      (libsource (lib "eagle-import") (part "R-EU_0204/7"))
    )
    (comp (ref "RIR3")
      (value "R-EU_0204/7")
      (footprint "eagle-import:0204_7")
      (libsource (lib "eagle-import") (part "R-EU_0204/7"))
    )
    (comp (ref "RIR4")
      (value "R-EU_0204/7")
      (footprint "eagle-import:0204_7")
      (libsource (lib "eagle-import") (part "R-EU_0204/7"))
    )
    (comp (ref "RIR5")
      (value "R-EU_0204/7")
      (footprint "eagle-import:0204_7")
      (libsource (lib "eagle-import") (part "R-EU_0204/7"))
    )
    (comp (ref "RIR6")
      (value "R-EU_0204/7")
      (footprint "eagle-import:0204_7")
      (libsource (lib "eagle-import") (part "R-EU_0204/7"))
    )
    (comp (ref "RIR7")
      (value "R-EU_0204/7")
      (footprint "eagle-import:0204_7")
      (libsource (lib "eagle-import") (part "R-EU_0204/7"))
    )
    (comp (ref "D8")
      (value "74138N")
      (footprint "eagle-import:DIL16")
      (libsource (lib "eagle-import") (part "74138N"))
    )
    (comp (ref "NOA")
      (value "LED5MM")
      (footprint "eagle-import:LED5MM")
      (libsource (lib "eagle-import") (part "LED5MM"))
    )
    (comp (ref "NOV")
      (value "LED5MM")
      (footprint "eagle-import:LED5MM")
      (libsource (lib "eagle-import") (part "LED5MM"))
    )
    (comp (ref "NOX")
      (value "LED5MM")
      (footprint "eagle-import:LED5MM")
      (libsource (lib "eagle-import") (part "LED5MM"))
    )
    (comp (ref "NOY")
      (value "LED5MM")
      (footprint "eagle-import:LED5MM")
      (libsource (lib "eagle-import") (part "LED5MM"))
    )
    (comp (ref "RD61")
      (value "R-EU_0204/7")
      (footprint "eagle-import:0204_7")
      (libsource (lib "eagle-import") (part "R-EU_0204/7"))
    )
    (comp (ref "RD62")
      (value "R-EU_0204/7")
      (footprint "eagle-import:0204_7")
      (libsource (lib "eagle-import") (part "R-EU_0204/7"))
    )
    (comp (ref "RD63")
      (value "R-EU_0204/7")
      (footprint "eagle-import:0204_7")
      (libsource (lib "eagle-import") (part "R-EU_0204/7"))
    )
    (comp (ref "RD64")
      (value "R-EU_0204/7")
      (footprint "eagle-import:0204_7")
      (libsource (lib "eagle-import") (part "R-EU_0204/7"))
    )
    (comp (ref "RD65")
      (value "R-EU_0204/7")
      (footprint "eagle-import:0204_7")
      (libsource (lib "eagle-import") (part "R-EU_0204/7"))
    )
    (comp (ref "RD66")
      (value "R-EU_0204/7")
      (footprint "eagle-import:0204_7")
      (libsource (lib "eagle-import") (part "R-EU_0204/7"))
    )
    (comp (ref "RD67")
      (value "R-EU_0204/7")
      (footprint "eagle-import:0204_7")
      (libsource (lib "eagle-import") (part "R-EU_0204/7"))
    )
    (comp (ref "RD68")
      (value "R-EU_0204/7")
      (footprint "eagle-import:0204_7")
      (libsource (lib "eagle-import") (part "R-EU_0204/7"))
    )
    (comp (ref "XOA")
      (value "LED5MM")
      (footprint "eagle-import:LED5MM")
      (libsource (lib "eagle-import") (part "LED5MM"))
    )
    (comp (ref "XOV")
      (value "LED5MM")
      (footprint "eagle-import:LED5MM")
      (libsource (lib "eagle-import") (part "LED5MM"))
    )
    (comp (ref "XOX")
      (value "LED5MM")
      (footprint "eagle-import:LED5MM")
      (libsource (lib "eagle-import") (part "LED5MM"))
    )
    (comp (ref "XOY")
      (value "LED5MM")
      (footprint "eagle-import:LED5MM")
      (libsource (lib "eagle-import") (part "LED5MM"))
    )
  )
  (nets
    (net (code "1") (name "ADA") (class "Default")
      (node (ref "D3") (pin "13") (pinfunction "Y2_13") (pintype "output"))
      (node (ref "INC3") (pin "3") (pinfunction "3_3") (pintype "passive"))
      (node (ref "RD33") (pin "2") (pinfunction "2_2") (pintype "passive"))
    )
    (net (code "2") (name "ADI") (class "Default")
      (node (ref "D3") (pin "12") (pinfunction "Y3_12") (pintype "output"))
      (node (ref "INC3") (pin "2") (pinfunction "2_2") (pintype "passive"))
      (node (ref "RD34") (pin "2") (pinfunction "2_2") (pintype "passive"))
    )
    (net (code "3") (name "ADV") (class "Default")
      (node (ref "D3") (pin "11") (pinfunction "Y4_11") (pintype "output"))
      (node (ref "INC3") (pin "1") (pinfunction "1_1") (pintype "passive"))
      (node (ref "RD35") (pin "2") (pinfunction "2_2") (pintype "passive"))
    )
    (net (code "4") (name "ADX") (class "Default")
      (node (ref "D3") (pin "15") (pinfunction "Y0_15") (pintype "output"))
      (node (ref "INC3") (pin "5") (pinfunction "5_5") (pintype "passive"))
      (node (ref "RD31") (pin "2") (pinfunction "2_2") (pintype "passive"))
    )
    (net (code "5") (name "ADY") (class "Default")
      (node (ref "D3") (pin "14") (pinfunction "Y1_14") (pintype "output"))
      (node (ref "INC3") (pin "4") (pinfunction "4_4") (pintype "passive"))
      (node (ref "RD32") (pin "2") (pinfunction "2_2") (pintype "passive"))
    )
    (net (code "6") (name "ANA") (class "Default")
      (node (ref "D7") (pin "13") (pinfunction "Y2_13") (pintype "output"))
      (node (ref "INC7") (pin "6") (pinfunction "6_6") (pintype "passive"))
      (node (ref "RD55") (pin "2") (pinfunction "2_2") (pintype "passive"))
    )
    (net (code "7") (name "ANV") (class "Default")
      (node (ref "D7") (pin "12") (pinfunction "Y3_12") (pintype "output"))
      (node (ref "INC7") (pin "5") (pinfunction "5_5") (pintype "passive"))
      (node (ref "RD56") (pin "2") (pinfunction "2_2") (pintype "passive"))
    )
    (net (code "8") (name "ANX") (class "Default")
      (node (ref "D7") (pin "15") (pinfunction "Y0_15") (pintype "output"))
      (node (ref "INC7") (pin "8") (pinfunction "8_8") (pintype "passive"))
      (node (ref "RD53") (pin "2") (pinfunction "2_2") (pintype "passive"))
    )
    (net (code "9") (name "ANY") (class "Default")
      (node (ref "D7") (pin "14") (pinfunction "Y1_14") (pintype "output"))
      (node (ref "INC7") (pin "7") (pinfunction "7_7") (pintype "passive"))
      (node (ref "RD54") (pin "2") (pinfunction "2_2") (pintype "passive"))
    )
    (net (code "10") (name "B0") (class "Default")
      (node (ref "BUS") (pin "8") (pinfunction "8_8") (pintype "passive"))
      (node (ref "IR") (pin "3") (pinfunction "1D_3") (pintype "input"))
    )
    (net (code "11") (name "B1") (class "Default")
      (node (ref "BUS") (pin "7") (pinfunction "7_7") (pintype "passive"))
      (node (ref "IR") (pin "4") (pinfunction "2D_4") (pintype "input"))
    )
    (net (code "12") (name "B2") (class "Default")
      (node (ref "BUS") (pin "6") (pinfunction "6_6") (pintype "passive"))
      (node (ref "IR") (pin "7") (pinfunction "3D_7") (pintype "input"))
    )
    (net (code "13") (name "B3") (class "Default")
      (node (ref "BUS") (pin "5") (pinfunction "5_5") (pintype "passive"))
      (node (ref "IR") (pin "8") (pinfunction "4D_8") (pintype "input"))
    )
    (net (code "14") (name "B4") (class "Default")
      (node (ref "BUS") (pin "4") (pinfunction "4_4") (pintype "passive"))
      (node (ref "IR") (pin "13") (pinfunction "5D_13") (pintype "input"))
    )
    (net (code "15") (name "B5") (class "Default")
      (node (ref "BUS") (pin "3") (pinfunction "3_3") (pintype "passive"))
      (node (ref "IR") (pin "14") (pinfunction "6D_14") (pintype "input"))
    )
    (net (code "16") (name "B6") (class "Default")
      (node (ref "BUS") (pin "2") (pinfunction "2_2") (pintype "passive"))
      (node (ref "IR") (pin "17") (pinfunction "7D_17") (pintype "input"))
    )
    (net (code "17") (name "B7") (class "Default")
      (node (ref "BUS") (pin "1") (pinfunction "1_1") (pintype "passive"))
      (node (ref "IR") (pin "18") (pinfunction "8D_18") (pintype "input"))
    )
    (net (code "18") (name "CALL") (class "Default")
      (node (ref "D1") (pin "11") (pinfunction "Y4_11") (pintype "output"))
      (node (ref "INC1") (pin "4") (pinfunction "4_4") (pintype "passive"))
      (node (ref "RD19") (pin "2") (pinfunction "2_2") (pintype "passive"))
    )
    (net (code "19") (name "CLA") (class "Default")
      (node (ref "D0") (pin "12") (pinfunction "Y3_12") (pintype "output"))
      (node (ref "INC0") (pin "4") (pinfunction "4_4") (pintype "passive"))
      (node (ref "RD11") (pin "2") (pinfunction "2_2") (pintype "passive"))
    )
    (net (code "20") (name "CLX") (class "Default")
      (node (ref "D0") (pin "14") (pinfunction "Y1_14") (pintype "output"))
      (node (ref "INC0") (pin "6") (pinfunction "6_6") (pintype "passive"))
      (node (ref "RD9") (pin "2") (pinfunction "2_2") (pintype "passive"))
    )
    (net (code "21") (name "CLY") (class "Default")
      (node (ref "D0") (pin "13") (pinfunction "Y2_13") (pintype "output"))
      (node (ref "INC0") (pin "5") (pinfunction "5_5") (pintype "passive"))
      (node (ref "RD10") (pin "2") (pinfunction "2_2") (pintype "passive"))
    )
    (net (code "22") (name "CMA") (class "Default")
      (node (ref "D1") (pin "13") (pinfunction "Y2_13") (pintype "output"))
      (node (ref "INC1") (pin "6") (pinfunction "6_6") (pintype "passive"))
      (node (ref "RD17") (pin "2") (pinfunction "2_2") (pintype "passive"))
    )
    (net (code "23") (name "CMV") (class "Default")
      (node (ref "D1") (pin "12") (pinfunction "Y3_12") (pintype "output"))
      (node (ref "INC1") (pin "5") (pinfunction "5_5") (pintype "passive"))
      (node (ref "RD18") (pin "2") (pinfunction "2_2") (pintype "passive"))
    )
    (net (code "24") (name "CMX") (class "Default")
      (node (ref "D1") (pin "15") (pinfunction "Y0_15") (pintype "output"))
      (node (ref "INC1") (pin "8") (pinfunction "8_8") (pintype "passive"))
      (node (ref "RD15") (pin "2") (pinfunction "2_2") (pintype "passive"))
    )
    (net (code "25") (name "CMY") (class "Default")
      (node (ref "D1") (pin "14") (pinfunction "Y1_14") (pintype "output"))
      (node (ref "INC1") (pin "7") (pinfunction "7_7") (pintype "passive"))
      (node (ref "RD16") (pin "2") (pinfunction "2_2") (pintype "passive"))
    )
    (net (code "26") (name "D0") (class "Default")
      (node (ref "D0") (pin "4") (pinfunction "~{G2A}_4") (pintype "input"))
      (node (ref "D0") (pin "5") (pinfunction "~{G2B}_5") (pintype "input"))
      (node (ref "RD0") (pin "2") (pinfunction "2_2") (pintype "passive"))
      (node (ref "SELECTOR") (pin "15") (pinfunction "Y0_15") (pintype "output"))
    )
    (net (code "27") (name "D1") (class "Default")
      (node (ref "D1") (pin "4") (pinfunction "~{G2A}_4") (pintype "input"))
      (node (ref "D1") (pin "5") (pinfunction "~{G2B}_5") (pintype "input"))
      (node (ref "RD1") (pin "2") (pinfunction "2_2") (pintype "passive"))
      (node (ref "SELECTOR") (pin "14") (pinfunction "Y1_14") (pintype "output"))
    )
    (net (code "28") (name "D2") (class "Default")
      (node (ref "D2") (pin "4") (pinfunction "~{G2A}_4") (pintype "input"))
      (node (ref "D2") (pin "5") (pinfunction "~{G2B}_5") (pintype "input"))
      (node (ref "RD2") (pin "2") (pinfunction "2_2") (pintype "passive"))
      (node (ref "SELECTOR") (pin "13") (pinfunction "Y2_13") (pintype "output"))
    )
    (net (code "29") (name "D3") (class "Default")
      (node (ref "D3") (pin "4") (pinfunction "~{G2A}_4") (pintype "input"))
      (node (ref "D3") (pin "5") (pinfunction "~{G2B}_5") (pintype "input"))
      (node (ref "RD3") (pin "2") (pinfunction "2_2") (pintype "passive"))
      (node (ref "SELECTOR") (pin "12") (pinfunction "Y3_12") (pintype "output"))
    )
    (net (code "30") (name "D4") (class "Default")
      (node (ref "D4") (pin "4") (pinfunction "~{G2A}_4") (pintype "input"))
      (node (ref "D4") (pin "5") (pinfunction "~{G2B}_5") (pintype "input"))
      (node (ref "RD4") (pin "2") (pinfunction "2_2") (pintype "passive"))
      (node (ref "SELECTOR") (pin "11") (pinfunction "Y4_11") (pintype "output"))
    )
    (net (code "31") (name "D5") (class "Default")
      (node (ref "D5") (pin "4") (pinfunction "~{G2A}_4") (pintype "input"))
      (node (ref "D5") (pin "5") (pinfunction "~{G2B}_5") (pintype "input"))
      (node (ref "RD5") (pin "2") (pinfunction "2_2") (pintype "passive"))
      (node (ref "SELECTOR") (pin "10") (pinfunction "Y5_10") (pintype "output"))
    )
    (net (code "32") (name "D6") (class "Default")
      (node (ref "D6") (pin "4") (pinfunction "~{G2A}_4") (pintype "input"))
      (node (ref "D6") (pin "5") (pinfunction "~{G2B}_5") (pintype "input"))
      (node (ref "RD6") (pin "2") (pinfunction "2_2") (pintype "passive"))
      (node (ref "SELECTOR") (pin "9") (pinfunction "Y6_9") (pintype "output"))
    )
    (net (code "33") (name "D7") (class "Default")
      (node (ref "D7") (pin "4") (pinfunction "~{G2A}_4") (pintype "input"))
      (node (ref "D7") (pin "5") (pinfunction "~{G2B}_5") (pintype "input"))
      (node (ref "RD7") (pin "2") (pinfunction "2_2") (pintype "passive"))
      (node (ref "SELECTOR") (pin "7") (pinfunction "Y7_7") (pintype "output"))
    )
    (net (code "34") (name "GND") (class "Default")
      (node (ref "ADA") (pin "K") (pinfunction "C_K") (pintype "passive"))
      (node (ref "ADI") (pin "K") (pinfunction "C_K") (pintype "passive"))
      (node (ref "ADV") (pin "K") (pinfunction "C_K") (pintype "passive"))
      (node (ref "ADX") (pin "K") (pinfunction "C_K") (pintype "passive"))
      (node (ref "ADY") (pin "K") (pinfunction "C_K") (pintype "passive"))
      (node (ref "ANA") (pin "K") (pinfunction "C_K") (pintype "passive"))
      (node (ref "ANV") (pin "K") (pinfunction "C_K") (pintype "passive"))
      (node (ref "ANX") (pin "K") (pinfunction "C_K") (pintype "passive"))
      (node (ref "ANY") (pin "K") (pinfunction "C_K") (pintype "passive"))
      (node (ref "C1") (pin "-") (pinfunction "-_-") (pintype "passive"))
      (node (ref "C10") (pin "-") (pinfunction "-_-") (pintype "passive"))
      (node (ref "C11") (pin "-") (pinfunction "-_-") (pintype "passive"))
      (node (ref "C2") (pin "-") (pinfunction "-_-") (pintype "passive"))
      (node (ref "C3") (pin "-") (pinfunction "-_-") (pintype "passive"))
      (node (ref "C4") (pin "-") (pinfunction "-_-") (pintype "passive"))
      (node (ref "C5") (pin "-") (pinfunction "-_-") (pintype "passive"))
      (node (ref "C6") (pin "-") (pinfunction "-_-") (pintype "passive"))
      (node (ref "C7") (pin "-") (pinfunction "-_-") (pintype "passive"))
      (node (ref "C8") (pin "-") (pinfunction "-_-") (pintype "passive"))
      (node (ref "C9") (pin "-") (pinfunction "-_-") (pintype "passive"))
      (node (ref "CALL") (pin "K") (pinfunction "C_K") (pintype "passive"))
      (node (ref "CLA") (pin "K") (pinfunction "C_K") (pintype "passive"))
      (node (ref "CLX") (pin "K") (pinfunction "C_K") (pintype "passive"))
      (node (ref "CLY") (pin "K") (pinfunction "C_K") (pintype "passive"))
      (node (ref "CMA") (pin "K") (pinfunction "C_K") (pintype "passive"))
      (node (ref "CMV") (pin "K") (pinfunction "C_K") (pintype "passive"))
      (node (ref "CMX") (pin "K") (pinfunction "C_K") (pintype "passive"))
      (node (ref "CMY") (pin "K") (pinfunction "C_K") (pintype "passive"))
      (node (ref "D0") (pin "8") (pinfunction "-UB_8") (pintype "power_in"))
      (node (ref "D1") (pin "8") (pinfunction "-UB_8") (pintype "power_in"))
      (node (ref "D2") (pin "8") (pinfunction "-UB_8") (pintype "power_in"))
      (node (ref "D3") (pin "8") (pinfunction "-UB_8") (pintype "power_in"))
      (node (ref "D4") (pin "8") (pinfunction "-UB_8") (pintype "power_in"))
      (node (ref "D5") (pin "8") (pinfunction "-UB_8") (pintype "power_in"))
      (node (ref "D6") (pin "8") (pinfunction "-UB_8") (pintype "power_in"))
      (node (ref "D7") (pin "8") (pinfunction "-UB_8") (pintype "power_in"))
      (node (ref "D8") (pin "8") (pinfunction "-UB_8") (pintype "power_in"))
      (node (ref "HLT") (pin "K") (pinfunction "C_K") (pintype "passive"))
      (node (ref "IR") (pin "10") (pinfunction "-UB_10") (pintype "power_in"))
      (node (ref "JE") (pin "K") (pinfunction "C_K") (pintype "passive"))
      (node (ref "JG") (pin "K") (pinfunction "C_K") (pintype "passive"))
      (node (ref "JL") (pin "K") (pinfunction "C_K") (pintype "passive"))
      (node (ref "JN") (pin "K") (pinfunction "C_K") (pintype "passive"))
      (node (ref "JNZ") (pin "K") (pinfunction "C_K") (pintype "passive"))
      (node (ref "JZ") (pin "K") (pinfunction "C_K") (pintype "passive"))
      (node (ref "LD0") (pin "K") (pinfunction "C_K") (pintype "passive"))
      (node (ref "LD1") (pin "K") (pinfunction "C_K") (pintype "passive"))
      (node (ref "LD2") (pin "K") (pinfunction "C_K") (pintype "passive"))
      (node (ref "LD3") (pin "K") (pinfunction "C_K") (pintype "passive"))
      (node (ref "LD4") (pin "K") (pinfunction "C_K") (pintype "passive"))
      (node (ref "LD5") (pin "K") (pinfunction "C_K") (pintype "passive"))
      (node (ref "LD6") (pin "K") (pinfunction "C_K") (pintype "passive"))
      (node (ref "LD7") (pin "K") (pinfunction "C_K") (pintype "passive"))
      (node (ref "LDA") (pin "K") (pinfunction "C_K") (pintype "passive"))
      (node (ref "LDAI") (pin "K") (pinfunction "C_K") (pintype "passive"))
      (node (ref "LDX") (pin "K") (pinfunction "C_K") (pintype "passive"))
      (node (ref "LDXI") (pin "K") (pinfunction "C_K") (pintype "passive"))
      (node (ref "LDY") (pin "K") (pinfunction "C_K") (pintype "passive"))
      (node (ref "LDYI") (pin "K") (pinfunction "C_K") (pintype "passive"))
      (node (ref "LIR0") (pin "K") (pinfunction "C_K") (pintype "passive"))
      (node (ref "LIR1") (pin "K") (pinfunction "C_K") (pintype "passive"))
      (node (ref "LIR2") (pin "K") (pinfunction "C_K") (pintype "passive"))
      (node (ref "LIR3") (pin "K") (pinfunction "C_K") (pintype "passive"))
      (node (ref "LIR4") (pin "K") (pinfunction "C_K") (pintype "passive"))
      (node (ref "LIR5") (pin "K") (pinfunction "C_K") (pintype "passive"))
      (node (ref "LIR6") (pin "K") (pinfunction "C_K") (pintype "passive"))
      (node (ref "LIR7") (pin "K") (pinfunction "C_K") (pintype "passive"))
      (node (ref "MAX") (pin "K") (pinfunction "C_K") (pintype "passive"))
      (node (ref "MAY") (pin "K") (pinfunction "C_K") (pintype "passive"))
      (node (ref "MXA") (pin "K") (pinfunction "C_K") (pintype "passive"))
      (node (ref "MXY") (pin "K") (pinfunction "C_K") (pintype "passive"))
      (node (ref "MYA") (pin "K") (pinfunction "C_K") (pintype "passive"))
      (node (ref "MYX") (pin "K") (pinfunction "C_K") (pintype "passive"))
      (node (ref "NOA") (pin "K") (pinfunction "C_K") (pintype "passive"))
      (node (ref "NOP") (pin "K") (pinfunction "C_K") (pintype "passive"))
      (node (ref "NOV") (pin "K") (pinfunction "C_K") (pintype "passive"))
      (node (ref "NOX") (pin "K") (pinfunction "C_K") (pintype "passive"))
      (node (ref "NOY") (pin "K") (pinfunction "C_K") (pintype "passive"))
      (node (ref "ORA") (pin "K") (pinfunction "C_K") (pintype "passive"))
      (node (ref "ORV") (pin "K") (pinfunction "C_K") (pintype "passive"))
      (node (ref "ORX") (pin "K") (pinfunction "C_K") (pintype "passive"))
      (node (ref "ORY") (pin "K") (pinfunction "C_K") (pintype "passive"))
      (node (ref "OUA") (pin "K") (pinfunction "C_K") (pintype "passive"))
      (node (ref "OUX") (pin "K") (pinfunction "C_K") (pintype "passive"))
      (node (ref "OUY") (pin "K") (pinfunction "C_K") (pintype "passive"))
      (node (ref "PS") (pin "1") (pinfunction "1_1") (pintype "passive"))
      (node (ref "RET") (pin "K") (pinfunction "C_K") (pintype "passive"))
      (node (ref "SELECTOR") (pin "8") (pinfunction "-UB_8") (pintype "power_in"))
      (node (ref "STA") (pin "K") (pinfunction "C_K") (pintype "passive"))
      (node (ref "STX") (pin "K") (pinfunction "C_K") (pintype "passive"))
      (node (ref "STY") (pin "K") (pinfunction "C_K") (pintype "passive"))
      (node (ref "SUA") (pin "K") (pinfunction "C_K") (pintype "passive"))
      (node (ref "SUI") (pin "K") (pinfunction "C_K") (pintype "passive"))
      (node (ref "SUV") (pin "K") (pinfunction "C_K") (pintype "passive"))
      (node (ref "SUX") (pin "K") (pinfunction "C_K") (pintype "passive"))
      (node (ref "SUY") (pin "K") (pinfunction "C_K") (pintype "passive"))
      (node (ref "XOA") (pin "K") (pinfunction "C_K") (pintype "passive"))
      (node (ref "XOV") (pin "K") (pinfunction "C_K") (pintype "passive"))
      (node (ref "XOX") (pin "K") (pinfunction "C_K") (pintype "passive"))
      (node (ref "XOY") (pin "K") (pinfunction "C_K") (pintype "passive"))
    )
    (net (code "35") (name "HLT") (class "Default")
      (node (ref "D2") (pin "7") (pinfunction "Y7_7") (pintype "output"))
      (node (ref "INC2") (pin "1") (pinfunction "1_1") (pintype "passive"))
      (node (ref "RD30") (pin "2") (pinfunction "2_2") (pintype "passive"))
    )
    (net (code "36") (name "IR-CP") (class "Default")
      (node (ref "CP") (pin "1") (pinfunction "1_1") (pintype "passive"))
      (node (ref "IR") (pin "11") (pinfunction "CLK_11") (pintype "input"))
    )
    (net (code "37") (name "IR0") (class "Default")
      (node (ref "D0") (pin "1") (pinfunction "A_1") (pintype "input"))
      (node (ref "D1") (pin "1") (pinfunction "A_1") (pintype "input"))
      (node (ref "D2") (pin "1") (pinfunction "A_1") (pintype "input"))
      (node (ref "D3") (pin "1") (pinfunction "A_1") (pintype "input"))
      (node (ref "D4") (pin "1") (pinfunction "A_1") (pintype "input"))
      (node (ref "D5") (pin "1") (pinfunction "A_1") (pintype "input"))
      (node (ref "D6") (pin "1") (pinfunction "A_1") (pintype "input"))
      (node (ref "D7") (pin "1") (pinfunction "A_1") (pintype "input"))
      (node (ref "D8") (pin "1") (pinfunction "A_1") (pintype "input"))
      (node (ref "IR") (pin "2") (pinfunction "1Q_2") (pintype "output"))
      (node (ref "RIR0") (pin "2") (pinfunction "2_2") (pintype "passive"))
    )
    (net (code "38") (name "IR1") (class "Default")
      (node (ref "D0") (pin "2") (pinfunction "B_2") (pintype "input"))
      (node (ref "D1") (pin "2") (pinfunction "B_2") (pintype "input"))
      (node (ref "D2") (pin "2") (pinfunction "B_2") (pintype "input"))
      (node (ref "D3") (pin "2") (pinfunction "B_2") (pintype "input"))
      (node (ref "D4") (pin "2") (pinfunction "B_2") (pintype "input"))
      (node (ref "D5") (pin "2") (pinfunction "B_2") (pintype "input"))
      (node (ref "D6") (pin "2") (pinfunction "B_2") (pintype "input"))
      (node (ref "D7") (pin "2") (pinfunction "B_2") (pintype "input"))
      (node (ref "D8") (pin "2") (pinfunction "B_2") (pintype "input"))
      (node (ref "IR") (pin "5") (pinfunction "2Q_5") (pintype "output"))
      (node (ref "RIR1") (pin "2") (pinfunction "2_2") (pintype "passive"))
    )
    (net (code "39") (name "IR2") (class "Default")
      (node (ref "D0") (pin "3") (pinfunction "C_3") (pintype "input"))
      (node (ref "D1") (pin "3") (pinfunction "C_3") (pintype "input"))
      (node (ref "D2") (pin "3") (pinfunction "C_3") (pintype "input"))
      (node (ref "D3") (pin "3") (pinfunction "C_3") (pintype "input"))
      (node (ref "D4") (pin "3") (pinfunction "C_3") (pintype "input"))
      (node (ref "D5") (pin "3") (pinfunction "C_3") (pintype "input"))
      (node (ref "D6") (pin "3") (pinfunction "C_3") (pintype "input"))
      (node (ref "D7") (pin "3") (pinfunction "C_3") (pintype "input"))
      (node (ref "D8") (pin "3") (pinfunction "C_3") (pintype "input"))
      (node (ref "IR") (pin "6") (pinfunction "3Q_6") (pintype "output"))
      (node (ref "RIR2") (pin "2") (pinfunction "2_2") (pintype "passive"))
    )
    (net (code "40") (name "IR3") (class "Default")
      (node (ref "IR") (pin "9") (pinfunction "4Q_9") (pintype "output"))
      (node (ref "RIR3") (pin "2") (pinfunction "2_2") (pintype "passive"))
      (node (ref "SELECTOR") (pin "1") (pinfunction "A_1") (pintype "input"))
    )
    (net (code "41") (name "IR4") (class "Default")
      (node (ref "IR") (pin "12") (pinfunction "5Q_12") (pintype "output"))
      (node (ref "RIR4") (pin "2") (pinfunction "2_2") (pintype "passive"))
      (node (ref "SELECTOR") (pin "2") (pinfunction "B_2") (pintype "input"))
    )
    (net (code "42") (name "IR5") (class "Default")
      (node (ref "IR") (pin "15") (pinfunction "6Q_15") (pintype "output"))
      (node (ref "RIR5") (pin "2") (pinfunction "2_2") (pintype "passive"))
      (node (ref "SELECTOR") (pin "3") (pinfunction "C_3") (pintype "input"))
    )
    (net (code "43") (name "IR6") (class "Default")
      (node (ref "IR") (pin "16") (pinfunction "7Q_16") (pintype "output"))
      (node (ref "RIR6") (pin "2") (pinfunction "2_2") (pintype "passive"))
      (node (ref "SELECTOR") (pin "4") (pinfunction "~{G2A}_4") (pintype "input"))
      (node (ref "SELECTOR") (pin "5") (pinfunction "~{G2B}_5") (pintype "input"))
    )
    (net (code "44") (name "IR7") (class "Default")
      (node (ref "D8") (pin "4") (pinfunction "~{G2A}_4") (pintype "input"))
      (node (ref "D8") (pin "5") (pinfunction "~{G2B}_5") (pintype "input"))
      (node (ref "IR") (pin "19") (pinfunction "8Q_19") (pintype "output"))
      (node (ref "RIR7") (pin "2") (pinfunction "2_2") (pintype "passive"))
    )
    (net (code "45") (name "JE") (class "Default")
      (node (ref "D2") (pin "10") (pinfunction "Y5_10") (pintype "output"))
      (node (ref "INC2") (pin "3") (pinfunction "3_3") (pintype "passive"))
      (node (ref "RD28") (pin "2") (pinfunction "2_2") (pintype "passive"))
    )
    (net (code "46") (name "JG") (class "Default")
      (node (ref "D2") (pin "11") (pinfunction "Y4_11") (pintype "output"))
      (node (ref "INC2") (pin "4") (pinfunction "4_4") (pintype "passive"))
      (node (ref "RD27") (pin "2") (pinfunction "2_2") (pintype "passive"))
    )
    (net (code "47") (name "JL") (class "Default")
      (node (ref "D2") (pin "12") (pinfunction "Y3_12") (pintype "output"))
      (node (ref "INC2") (pin "5") (pinfunction "5_5") (pintype "passive"))
      (node (ref "RD26") (pin "2") (pinfunction "2_2") (pintype "passive"))
    )
    (net (code "48") (name "JN") (class "Default")
      (node (ref "D2") (pin "13") (pinfunction "Y2_13") (pintype "output"))
      (node (ref "INC2") (pin "6") (pinfunction "6_6") (pintype "passive"))
      (node (ref "RD25") (pin "2") (pinfunction "2_2") (pintype "passive"))
    )
    (net (code "49") (name "JNZ") (class "Default")
      (node (ref "D2") (pin "14") (pinfunction "Y1_14") (pintype "output"))
      (node (ref "INC2") (pin "7") (pinfunction "7_7") (pintype "passive"))
      (node (ref "RD24") (pin "2") (pinfunction "2_2") (pintype "passive"))
    )
    (net (code "50") (name "JZ") (class "Default")
      (node (ref "D2") (pin "15") (pinfunction "Y0_15") (pintype "output"))
      (node (ref "INC2") (pin "8") (pinfunction "8_8") (pintype "passive"))
      (node (ref "RD23") (pin "2") (pinfunction "2_2") (pintype "passive"))
    )
    (net (code "51") (name "LDA") (class "Default")
      (node (ref "D5") (pin "13") (pinfunction "Y2_13") (pintype "output"))
      (node (ref "INC5") (pin "4") (pinfunction "4_4") (pintype "passive"))
      (node (ref "RD43") (pin "2") (pinfunction "2_2") (pintype "passive"))
    )
    (net (code "52") (name "LDAI") (class "Default")
      (node (ref "D5") (pin "10") (pinfunction "Y5_10") (pintype "output"))
      (node (ref "INC5") (pin "1") (pinfunction "1_1") (pintype "passive"))
      (node (ref "RD46") (pin "2") (pinfunction "2_2") (pintype "passive"))
    )
    (net (code "53") (name "LDX") (class "Default")
      (node (ref "D5") (pin "15") (pinfunction "Y0_15") (pintype "output"))
      (node (ref "INC5") (pin "6") (pinfunction "6_6") (pintype "passive"))
      (node (ref "RD41") (pin "2") (pinfunction "2_2") (pintype "passive"))
    )
    (net (code "54") (name "LDXI") (class "Default")
      (node (ref "D5") (pin "12") (pinfunction "Y3_12") (pintype "output"))
      (node (ref "INC5") (pin "3") (pinfunction "3_3") (pintype "passive"))
      (node (ref "RD44") (pin "2") (pinfunction "2_2") (pintype "passive"))
    )
    (net (code "55") (name "LDY") (class "Default")
      (node (ref "D5") (pin "14") (pinfunction "Y1_14") (pintype "output"))
      (node (ref "INC5") (pin "5") (pinfunction "5_5") (pintype "passive"))
      (node (ref "RD42") (pin "2") (pinfunction "2_2") (pintype "passive"))
    )
    (net (code "56") (name "LDYI") (class "Default")
      (node (ref "D5") (pin "11") (pinfunction "Y4_11") (pintype "output"))
      (node (ref "INC5") (pin "2") (pinfunction "2_2") (pintype "passive"))
      (node (ref "RD45") (pin "2") (pinfunction "2_2") (pintype "passive"))
    )
    (net (code "57") (name "MAX") (class "Default")
      (node (ref "D6") (pin "11") (pinfunction "Y4_11") (pintype "output"))
      (node (ref "INC6") (pin "2") (pinfunction "2_2") (pintype "passive"))
      (node (ref "RD51") (pin "2") (pinfunction "2_2") (pintype "passive"))
    )
    (net (code "58") (name "MAY") (class "Default")
      (node (ref "D6") (pin "10") (pinfunction "Y5_10") (pintype "output"))
      (node (ref "INC6") (pin "1") (pinfunction "1_1") (pintype "passive"))
      (node (ref "RD52") (pin "2") (pinfunction "2_2") (pintype "passive"))
    )
    (net (code "59") (name "MXA") (class "Default")
      (node (ref "D6") (pin "14") (pinfunction "Y1_14") (pintype "output"))
      (node (ref "INC6") (pin "5") (pinfunction "5_5") (pintype "passive"))
      (node (ref "RD48") (pin "2") (pinfunction "2_2") (pintype "passive"))
    )
    (net (code "60") (name "MXY") (class "Default")
      (node (ref "D6") (pin "15") (pinfunction "Y0_15") (pintype "output"))
      (node (ref "INC6") (pin "6") (pinfunction "6_6") (pintype "passive"))
      (node (ref "RD47") (pin "2") (pinfunction "2_2") (pintype "passive"))
    )
    (net (code "61") (name "MYA") (class "Default")
      (node (ref "D6") (pin "12") (pinfunction "Y3_12") (pintype "output"))
      (node (ref "INC6") (pin "3") (pinfunction "3_3") (pintype "passive"))
      (node (ref "RD50") (pin "2") (pinfunction "2_2") (pintype "passive"))
    )
    (net (code "62") (name "MYX") (class "Default")
      (node (ref "D6") (pin "13") (pinfunction "Y2_13") (pintype "output"))
      (node (ref "INC6") (pin "4") (pinfunction "4_4") (pintype "passive"))
      (node (ref "RD49") (pin "2") (pinfunction "2_2") (pintype "passive"))
    )
    (net (code "63") (name "NOA") (class "Default")
      (node (ref "D8") (pin "9") (pinfunction "Y6_9") (pintype "output"))
      (node (ref "INC8") (pin "2") (pinfunction "2_2") (pintype "passive"))
      (node (ref "RD67") (pin "2") (pinfunction "2_2") (pintype "passive"))
    )
    (net (code "64") (name "NOP") (class "Default")
      (node (ref "D0") (pin "15") (pinfunction "Y0_15") (pintype "output"))
      (node (ref "INC0") (pin "7") (pinfunction "7_7") (pintype "passive"))
      (node (ref "RD8") (pin "2") (pinfunction "2_2") (pintype "passive"))
    )
    (net (code "65") (name "NOV") (class "Default")
      (node (ref "D8") (pin "7") (pinfunction "Y7_7") (pintype "output"))
      (node (ref "INC8") (pin "1") (pinfunction "1_1") (pintype "passive"))
      (node (ref "RD68") (pin "2") (pinfunction "2_2") (pintype "passive"))
    )
    (net (code "66") (name "NOX") (class "Default")
      (node (ref "D8") (pin "11") (pinfunction "Y4_11") (pintype "output"))
      (node (ref "INC8") (pin "4") (pinfunction "4_4") (pintype "passive"))
      (node (ref "RD65") (pin "2") (pinfunction "2_2") (pintype "passive"))
    )
    (net (code "67") (name "NOY") (class "Default")
      (node (ref "D8") (pin "10") (pinfunction "Y5_10") (pintype "output"))
      (node (ref "INC8") (pin "3") (pinfunction "3_3") (pintype "passive"))
      (node (ref "RD66") (pin "2") (pinfunction "2_2") (pintype "passive"))
    )
    (net (code "68") (name "Net-(ADA-PadA)") (class "Default")
      (node (ref "ADA") (pin "A") (pinfunction "A_A") (pintype "passive"))
      (node (ref "RD33") (pin "1") (pinfunction "1_1") (pintype "passive"))
    )
    (net (code "69") (name "Net-(ADI-PadA)") (class "Default")
      (node (ref "ADI") (pin "A") (pinfunction "A_A") (pintype "passive"))
      (node (ref "RD34") (pin "1") (pinfunction "1_1") (pintype "passive"))
    )
    (net (code "70") (name "Net-(ADV-PadA)") (class "Default")
      (node (ref "ADV") (pin "A") (pinfunction "A_A") (pintype "passive"))
      (node (ref "RD35") (pin "1") (pinfunction "1_1") (pintype "passive"))
    )
    (net (code "71") (name "Net-(ADX-PadA)") (class "Default")
      (node (ref "ADX") (pin "A") (pinfunction "A_A") (pintype "passive"))
      (node (ref "RD31") (pin "1") (pinfunction "1_1") (pintype "passive"))
    )
    (net (code "72") (name "Net-(ADY-PadA)") (class "Default")
      (node (ref "ADY") (pin "A") (pinfunction "A_A") (pintype "passive"))
      (node (ref "RD32") (pin "1") (pinfunction "1_1") (pintype "passive"))
    )
    (net (code "73") (name "Net-(ANA-PadA)") (class "Default")
      (node (ref "ANA") (pin "A") (pinfunction "A_A") (pintype "passive"))
      (node (ref "RD55") (pin "1") (pinfunction "1_1") (pintype "passive"))
    )
    (net (code "74") (name "Net-(ANV-PadA)") (class "Default")
      (node (ref "ANV") (pin "A") (pinfunction "A_A") (pintype "passive"))
      (node (ref "RD56") (pin "1") (pinfunction "1_1") (pintype "passive"))
    )
    (net (code "75") (name "Net-(ANX-PadA)") (class "Default")
      (node (ref "ANX") (pin "A") (pinfunction "A_A") (pintype "passive"))
      (node (ref "RD53") (pin "1") (pinfunction "1_1") (pintype "passive"))
    )
    (net (code "76") (name "Net-(ANY-PadA)") (class "Default")
      (node (ref "ANY") (pin "A") (pinfunction "A_A") (pintype "passive"))
      (node (ref "RD54") (pin "1") (pinfunction "1_1") (pintype "passive"))
    )
    (net (code "77") (name "Net-(CALL-PadA)") (class "Default")
      (node (ref "CALL") (pin "A") (pinfunction "A_A") (pintype "passive"))
      (node (ref "RD19") (pin "1") (pinfunction "1_1") (pintype "passive"))
    )
    (net (code "78") (name "Net-(CLA-PadA)") (class "Default")
      (node (ref "CLA") (pin "A") (pinfunction "A_A") (pintype "passive"))
      (node (ref "RD11") (pin "1") (pinfunction "1_1") (pintype "passive"))
    )
    (net (code "79") (name "Net-(CLX-PadA)") (class "Default")
      (node (ref "CLX") (pin "A") (pinfunction "A_A") (pintype "passive"))
      (node (ref "RD9") (pin "1") (pinfunction "1_1") (pintype "passive"))
    )
    (net (code "80") (name "Net-(CLY-PadA)") (class "Default")
      (node (ref "CLY") (pin "A") (pinfunction "A_A") (pintype "passive"))
      (node (ref "RD10") (pin "1") (pinfunction "1_1") (pintype "passive"))
    )
    (net (code "81") (name "Net-(CMA-PadA)") (class "Default")
      (node (ref "CMA") (pin "A") (pinfunction "A_A") (pintype "passive"))
      (node (ref "RD17") (pin "1") (pinfunction "1_1") (pintype "passive"))
    )
    (net (code "82") (name "Net-(CMV-PadA)") (class "Default")
      (node (ref "CMV") (pin "A") (pinfunction "A_A") (pintype "passive"))
      (node (ref "RD18") (pin "1") (pinfunction "1_1") (pintype "passive"))
    )
    (net (code "83") (name "Net-(CMX-PadA)") (class "Default")
      (node (ref "CMX") (pin "A") (pinfunction "A_A") (pintype "passive"))
      (node (ref "RD15") (pin "1") (pinfunction "1_1") (pintype "passive"))
    )
    (net (code "84") (name "Net-(CMY-PadA)") (class "Default")
      (node (ref "CMY") (pin "A") (pinfunction "A_A") (pintype "passive"))
      (node (ref "RD16") (pin "1") (pinfunction "1_1") (pintype "passive"))
    )
    (net (code "85") (name "Net-(HLT-PadA)") (class "Default")
      (node (ref "HLT") (pin "A") (pinfunction "A_A") (pintype "passive"))
      (node (ref "RD30") (pin "1") (pinfunction "1_1") (pintype "passive"))
    )
    (net (code "86") (name "Net-(JE-PadA)") (class "Default")
      (node (ref "JE") (pin "A") (pinfunction "A_A") (pintype "passive"))
      (node (ref "RD28") (pin "1") (pinfunction "1_1") (pintype "passive"))
    )
    (net (code "87") (name "Net-(JG-PadA)") (class "Default")
      (node (ref "JG") (pin "A") (pinfunction "A_A") (pintype "passive"))
      (node (ref "RD27") (pin "1") (pinfunction "1_1") (pintype "passive"))
    )
    (net (code "88") (name "Net-(JL-PadA)") (class "Default")
      (node (ref "JL") (pin "A") (pinfunction "A_A") (pintype "passive"))
      (node (ref "RD26") (pin "1") (pinfunction "1_1") (pintype "passive"))
    )
    (net (code "89") (name "Net-(JN-PadA)") (class "Default")
      (node (ref "JN") (pin "A") (pinfunction "A_A") (pintype "passive"))
      (node (ref "RD25") (pin "1") (pinfunction "1_1") (pintype "passive"))
    )
    (net (code "90") (name "Net-(JNZ-PadA)") (class "Default")
      (node (ref "JNZ") (pin "A") (pinfunction "A_A") (pintype "passive"))
      (node (ref "RD24") (pin "1") (pinfunction "1_1") (pintype "passive"))
    )
    (net (code "91") (name "Net-(JZ-PadA)") (class "Default")
      (node (ref "JZ") (pin "A") (pinfunction "A_A") (pintype "passive"))
      (node (ref "RD23") (pin "1") (pinfunction "1_1") (pintype "passive"))
    )
    (net (code "92") (name "Net-(LD0-PadA)") (class "Default")
      (node (ref "LD0") (pin "A") (pinfunction "A_A") (pintype "passive"))
      (node (ref "RD0") (pin "1") (pinfunction "1_1") (pintype "passive"))
    )
    (net (code "93") (name "Net-(LD1-PadA)") (class "Default")
      (node (ref "LD1") (pin "A") (pinfunction "A_A") (pintype "passive"))
      (node (ref "RD1") (pin "1") (pinfunction "1_1") (pintype "passive"))
    )
    (net (code "94") (name "Net-(LD2-PadA)") (class "Default")
      (node (ref "LD2") (pin "A") (pinfunction "A_A") (pintype "passive"))
      (node (ref "RD2") (pin "1") (pinfunction "1_1") (pintype "passive"))
    )
    (net (code "95") (name "Net-(LD3-PadA)") (class "Default")
      (node (ref "LD3") (pin "A") (pinfunction "A_A") (pintype "passive"))
      (node (ref "RD3") (pin "1") (pinfunction "1_1") (pintype "passive"))
    )
    (net (code "96") (name "Net-(LD4-PadA)") (class "Default")
      (node (ref "LD4") (pin "A") (pinfunction "A_A") (pintype "passive"))
      (node (ref "RD4") (pin "1") (pinfunction "1_1") (pintype "passive"))
    )
    (net (code "97") (name "Net-(LD5-PadA)") (class "Default")
      (node (ref "LD5") (pin "A") (pinfunction "A_A") (pintype "passive"))
      (node (ref "RD5") (pin "1") (pinfunction "1_1") (pintype "passive"))
    )
    (net (code "98") (name "Net-(LD6-PadA)") (class "Default")
      (node (ref "LD6") (pin "A") (pinfunction "A_A") (pintype "passive"))
      (node (ref "RD6") (pin "1") (pinfunction "1_1") (pintype "passive"))
    )
    (net (code "99") (name "Net-(LD7-PadA)") (class "Default")
      (node (ref "LD7") (pin "A") (pinfunction "A_A") (pintype "passive"))
      (node (ref "RD7") (pin "1") (pinfunction "1_1") (pintype "passive"))
    )
    (net (code "100") (name "Net-(LDA-PadA)") (class "Default")
      (node (ref "LDA") (pin "A") (pinfunction "A_A") (pintype "passive"))
      (node (ref "RD43") (pin "1") (pinfunction "1_1") (pintype "passive"))
    )
    (net (code "101") (name "Net-(LDAI-PadA)") (class "Default")
      (node (ref "LDAI") (pin "A") (pinfunction "A_A") (pintype "passive"))
      (node (ref "RD46") (pin "1") (pinfunction "1_1") (pintype "passive"))
    )
    (net (code "102") (name "Net-(LDX-PadA)") (class "Default")
      (node (ref "LDX") (pin "A") (pinfunction "A_A") (pintype "passive"))
      (node (ref "RD41") (pin "1") (pinfunction "1_1") (pintype "passive"))
    )
    (net (code "103") (name "Net-(LDXI-PadA)") (class "Default")
      (node (ref "LDXI") (pin "A") (pinfunction "A_A") (pintype "passive"))
      (node (ref "RD44") (pin "1") (pinfunction "1_1") (pintype "passive"))
    )
    (net (code "104") (name "Net-(LDY-PadA)") (class "Default")
      (node (ref "LDY") (pin "A") (pinfunction "A_A") (pintype "passive"))
      (node (ref "RD42") (pin "1") (pinfunction "1_1") (pintype "passive"))
    )
    (net (code "105") (name "Net-(LDYI-PadA)") (class "Default")
      (node (ref "LDYI") (pin "A") (pinfunction "A_A") (pintype "passive"))
      (node (ref "RD45") (pin "1") (pinfunction "1_1") (pintype "passive"))
    )
    (net (code "106") (name "Net-(LIR0-PadA)") (class "Default")
      (node (ref "LIR0") (pin "A") (pinfunction "A_A") (pintype "passive"))
      (node (ref "RIR0") (pin "1") (pinfunction "1_1") (pintype "passive"))
    )
    (net (code "107") (name "Net-(LIR1-PadA)") (class "Default")
      (node (ref "LIR1") (pin "A") (pinfunction "A_A") (pintype "passive"))
      (node (ref "RIR1") (pin "1") (pinfunction "1_1") (pintype "passive"))
    )
    (net (code "108") (name "Net-(LIR2-PadA)") (class "Default")
      (node (ref "LIR2") (pin "A") (pinfunction "A_A") (pintype "passive"))
      (node (ref "RIR2") (pin "1") (pinfunction "1_1") (pintype "passive"))
    )
    (net (code "109") (name "Net-(LIR3-PadA)") (class "Default")
      (node (ref "LIR3") (pin "A") (pinfunction "A_A") (pintype "passive"))
      (node (ref "RIR3") (pin "1") (pinfunction "1_1") (pintype "passive"))
    )
    (net (code "110") (name "Net-(LIR4-PadA)") (class "Default")
      (node (ref "LIR4") (pin "A") (pinfunction "A_A") (pintype "passive"))
      (node (ref "RIR4") (pin "1") (pinfunction "1_1") (pintype "passive"))
    )
    (net (code "111") (name "Net-(LIR5-PadA)") (class "Default")
      (node (ref "LIR5") (pin "A") (pinfunction "A_A") (pintype "passive"))
      (node (ref "RIR5") (pin "1") (pinfunction "1_1") (pintype "passive"))
    )
    (net (code "112") (name "Net-(LIR6-PadA)") (class "Default")
      (node (ref "LIR6") (pin "A") (pinfunction "A_A") (pintype "passive"))
      (node (ref "RIR6") (pin "1") (pinfunction "1_1") (pintype "passive"))
    )
    (net (code "113") (name "Net-(LIR7-PadA)") (class "Default")
      (node (ref "LIR7") (pin "A") (pinfunction "A_A") (pintype "passive"))
      (node (ref "RIR7") (pin "1") (pinfunction "1_1") (pintype "passive"))
    )
    (net (code "114") (name "Net-(MAX-PadA)") (class "Default")
      (node (ref "MAX") (pin "A") (pinfunction "A_A") (pintype "passive"))
      (node (ref "RD51") (pin "1") (pinfunction "1_1") (pintype "passive"))
    )
    (net (code "115") (name "Net-(MAY-PadA)") (class "Default")
      (node (ref "MAY") (pin "A") (pinfunction "A_A") (pintype "passive"))
      (node (ref "RD52") (pin "1") (pinfunction "1_1") (pintype "passive"))
    )
    (net (code "116") (name "Net-(MXA-PadA)") (class "Default")
      (node (ref "MXA") (pin "A") (pinfunction "A_A") (pintype "passive"))
      (node (ref "RD48") (pin "1") (pinfunction "1_1") (pintype "passive"))
    )
    (net (code "117") (name "Net-(MXY-PadA)") (class "Default")
      (node (ref "MXY") (pin "A") (pinfunction "A_A") (pintype "passive"))
      (node (ref "RD47") (pin "1") (pinfunction "1_1") (pintype "passive"))
    )
    (net (code "118") (name "Net-(MYA-PadA)") (class "Default")
      (node (ref "MYA") (pin "A") (pinfunction "A_A") (pintype "passive"))
      (node (ref "RD50") (pin "1") (pinfunction "1_1") (pintype "passive"))
    )
    (net (code "119") (name "Net-(MYX-PadA)") (class "Default")
      (node (ref "MYX") (pin "A") (pinfunction "A_A") (pintype "passive"))
      (node (ref "RD49") (pin "1") (pinfunction "1_1") (pintype "passive"))
    )
    (net (code "120") (name "Net-(NOA-PadA)") (class "Default")
      (node (ref "NOA") (pin "A") (pinfunction "A_A") (pintype "passive"))
      (node (ref "RD67") (pin "1") (pinfunction "1_1") (pintype "passive"))
    )
    (net (code "121") (name "Net-(NOP-PadA)") (class "Default")
      (node (ref "NOP") (pin "A") (pinfunction "A_A") (pintype "passive"))
      (node (ref "RD8") (pin "1") (pinfunction "1_1") (pintype "passive"))
    )
    (net (code "122") (name "Net-(NOV-PadA)") (class "Default")
      (node (ref "NOV") (pin "A") (pinfunction "A_A") (pintype "passive"))
      (node (ref "RD68") (pin "1") (pinfunction "1_1") (pintype "passive"))
    )
    (net (code "123") (name "Net-(NOX-PadA)") (class "Default")
      (node (ref "NOX") (pin "A") (pinfunction "A_A") (pintype "passive"))
      (node (ref "RD65") (pin "1") (pinfunction "1_1") (pintype "passive"))
    )
    (net (code "124") (name "Net-(NOY-PadA)") (class "Default")
      (node (ref "NOY") (pin "A") (pinfunction "A_A") (pintype "passive"))
      (node (ref "RD66") (pin "1") (pinfunction "1_1") (pintype "passive"))
    )
    (net (code "125") (name "Net-(ORA-PadA)") (class "Default")
      (node (ref "ORA") (pin "A") (pinfunction "A_A") (pintype "passive"))
      (node (ref "RD59") (pin "1") (pinfunction "1_1") (pintype "passive"))
    )
    (net (code "126") (name "Net-(ORV-PadA)") (class "Default")
      (node (ref "ORV") (pin "A") (pinfunction "A_A") (pintype "passive"))
      (node (ref "RD60") (pin "1") (pinfunction "1_1") (pintype "passive"))
    )
    (net (code "127") (name "Net-(ORX-PadA)") (class "Default")
      (node (ref "ORX") (pin "A") (pinfunction "A_A") (pintype "passive"))
      (node (ref "RD57") (pin "1") (pinfunction "1_1") (pintype "passive"))
    )
    (net (code "128") (name "Net-(ORY-PadA)") (class "Default")
      (node (ref "ORY") (pin "A") (pinfunction "A_A") (pintype "passive"))
      (node (ref "RD58") (pin "1") (pinfunction "1_1") (pintype "passive"))
    )
    (net (code "129") (name "Net-(OUA-PadA)") (class "Default")
      (node (ref "OUA") (pin "A") (pinfunction "A_A") (pintype "passive"))
      (node (ref "RD14") (pin "1") (pinfunction "1_1") (pintype "passive"))
    )
    (net (code "130") (name "Net-(OUX-PadA)") (class "Default")
      (node (ref "OUX") (pin "A") (pinfunction "A_A") (pintype "passive"))
      (node (ref "RD12") (pin "1") (pinfunction "1_1") (pintype "passive"))
    )
    (net (code "131") (name "Net-(OUY-PadA)") (class "Default")
      (node (ref "OUY") (pin "A") (pinfunction "A_A") (pintype "passive"))
      (node (ref "RD13") (pin "1") (pinfunction "1_1") (pintype "passive"))
    )
    (net (code "132") (name "Net-(RD20-Pad1)") (class "Default")
      (node (ref "RD20") (pin "1") (pinfunction "1_1") (pintype "passive"))
      (node (ref "STX") (pin "A") (pinfunction "A_A") (pintype "passive"))
    )
    (net (code "133") (name "Net-(RD21-Pad1)") (class "Default")
      (node (ref "RD21") (pin "1") (pinfunction "1_1") (pintype "passive"))
      (node (ref "STY") (pin "A") (pinfunction "A_A") (pintype "passive"))
    )
    (net (code "134") (name "Net-(RD22-Pad1)") (class "Default")
      (node (ref "RD22") (pin "1") (pinfunction "1_1") (pintype "passive"))
      (node (ref "STA") (pin "A") (pinfunction "A_A") (pintype "passive"))
    )
    (net (code "135") (name "Net-(RD29-Pad1)") (class "Default")
      (node (ref "RD29") (pin "1") (pinfunction "1_1") (pintype "passive"))
      (node (ref "RET") (pin "A") (pinfunction "A_A") (pintype "passive"))
    )
    (net (code "136") (name "Net-(RD36-Pad1)") (class "Default")
      (node (ref "RD36") (pin "1") (pinfunction "1_1") (pintype "passive"))
      (node (ref "SUX") (pin "A") (pinfunction "A_A") (pintype "passive"))
    )
    (net (code "137") (name "Net-(RD37-Pad1)") (class "Default")
      (node (ref "RD37") (pin "1") (pinfunction "1_1") (pintype "passive"))
      (node (ref "SUY") (pin "A") (pinfunction "A_A") (pintype "passive"))
    )
    (net (code "138") (name "Net-(RD38-Pad1)") (class "Default")
      (node (ref "RD38") (pin "1") (pinfunction "1_1") (pintype "passive"))
      (node (ref "SUA") (pin "A") (pinfunction "A_A") (pintype "passive"))
    )
    (net (code "139") (name "Net-(RD39-Pad1)") (class "Default")
      (node (ref "RD39") (pin "1") (pinfunction "1_1") (pintype "passive"))
      (node (ref "SUI") (pin "A") (pinfunction "A_A") (pintype "passive"))
    )
    (net (code "140") (name "Net-(RD40-Pad1)") (class "Default")
      (node (ref "RD40") (pin "1") (pinfunction "1_1") (pintype "passive"))
      (node (ref "SUV") (pin "A") (pinfunction "A_A") (pintype "passive"))
    )
    (net (code "141") (name "Net-(RD61-Pad1)") (class "Default")
      (node (ref "RD61") (pin "1") (pinfunction "1_1") (pintype "passive"))
      (node (ref "XOX") (pin "A") (pinfunction "A_A") (pintype "passive"))
    )
    (net (code "142") (name "Net-(RD62-Pad1)") (class "Default")
      (node (ref "RD62") (pin "1") (pinfunction "1_1") (pintype "passive"))
      (node (ref "XOY") (pin "A") (pinfunction "A_A") (pintype "passive"))
    )
    (net (code "143") (name "Net-(RD63-Pad1)") (class "Default")
      (node (ref "RD63") (pin "1") (pinfunction "1_1") (pintype "passive"))
      (node (ref "XOA") (pin "A") (pinfunction "A_A") (pintype "passive"))
    )
    (net (code "144") (name "Net-(RD64-Pad1)") (class "Default")
      (node (ref "RD64") (pin "1") (pinfunction "1_1") (pintype "passive"))
      (node (ref "XOV") (pin "A") (pinfunction "A_A") (pintype "passive"))
    )
    (net (code "145") (name "ORA") (class "Default")
      (node (ref "D7") (pin "9") (pinfunction "Y6_9") (pintype "output"))
      (node (ref "INC7") (pin "2") (pinfunction "2_2") (pintype "passive"))
      (node (ref "RD59") (pin "2") (pinfunction "2_2") (pintype "passive"))
    )
    (net (code "146") (name "ORV") (class "Default")
      (node (ref "D7") (pin "7") (pinfunction "Y7_7") (pintype "output"))
      (node (ref "INC7") (pin "1") (pinfunction "1_1") (pintype "passive"))
      (node (ref "RD60") (pin "2") (pinfunction "2_2") (pintype "passive"))
    )
    (net (code "147") (name "ORX") (class "Default")
      (node (ref "D7") (pin "11") (pinfunction "Y4_11") (pintype "output"))
      (node (ref "INC7") (pin "4") (pinfunction "4_4") (pintype "passive"))
      (node (ref "RD57") (pin "2") (pinfunction "2_2") (pintype "passive"))
    )
    (net (code "148") (name "ORY") (class "Default")
      (node (ref "D7") (pin "10") (pinfunction "Y5_10") (pintype "output"))
      (node (ref "INC7") (pin "3") (pinfunction "3_3") (pintype "passive"))
      (node (ref "RD58") (pin "2") (pinfunction "2_2") (pintype "passive"))
    )
    (net (code "149") (name "OUA") (class "Default")
      (node (ref "D0") (pin "9") (pinfunction "Y6_9") (pintype "output"))
      (node (ref "INC0") (pin "1") (pinfunction "1_1") (pintype "passive"))
      (node (ref "RD14") (pin "2") (pinfunction "2_2") (pintype "passive"))
    )
    (net (code "150") (name "OUX") (class "Default")
      (node (ref "D0") (pin "11") (pinfunction "Y4_11") (pintype "output"))
      (node (ref "INC0") (pin "3") (pinfunction "3_3") (pintype "passive"))
      (node (ref "RD12") (pin "2") (pinfunction "2_2") (pintype "passive"))
    )
    (net (code "151") (name "OUY") (class "Default")
      (node (ref "D0") (pin "10") (pinfunction "Y5_10") (pintype "output"))
      (node (ref "INC0") (pin "2") (pinfunction "2_2") (pintype "passive"))
      (node (ref "RD13") (pin "2") (pinfunction "2_2") (pintype "passive"))
    )
    (net (code "152") (name "RET") (class "Default")
      (node (ref "D2") (pin "9") (pinfunction "Y6_9") (pintype "output"))
      (node (ref "INC2") (pin "2") (pinfunction "2_2") (pintype "passive"))
      (node (ref "RD29") (pin "2") (pinfunction "2_2") (pintype "passive"))
    )
    (net (code "153") (name "STA") (class "Default")
      (node (ref "D1") (pin "7") (pinfunction "Y7_7") (pintype "output"))
      (node (ref "INC1") (pin "1") (pinfunction "1_1") (pintype "passive"))
      (node (ref "RD22") (pin "2") (pinfunction "2_2") (pintype "passive"))
    )
    (net (code "154") (name "STX") (class "Default")
      (node (ref "D1") (pin "10") (pinfunction "Y5_10") (pintype "output"))
      (node (ref "INC1") (pin "3") (pinfunction "3_3") (pintype "passive"))
      (node (ref "RD20") (pin "2") (pinfunction "2_2") (pintype "passive"))
    )
    (net (code "155") (name "STY") (class "Default")
      (node (ref "D1") (pin "9") (pinfunction "Y6_9") (pintype "output"))
      (node (ref "INC1") (pin "2") (pinfunction "2_2") (pintype "passive"))
      (node (ref "RD21") (pin "2") (pinfunction "2_2") (pintype "passive"))
    )
    (net (code "156") (name "SUA") (class "Default")
      (node (ref "D4") (pin "13") (pinfunction "Y2_13") (pintype "output"))
      (node (ref "INC4") (pin "3") (pinfunction "3_3") (pintype "passive"))
      (node (ref "RD38") (pin "2") (pinfunction "2_2") (pintype "passive"))
    )
    (net (code "157") (name "SUI") (class "Default")
      (node (ref "D4") (pin "12") (pinfunction "Y3_12") (pintype "output"))
      (node (ref "INC4") (pin "2") (pinfunction "2_2") (pintype "passive"))
      (node (ref "RD39") (pin "2") (pinfunction "2_2") (pintype "passive"))
    )
    (net (code "158") (name "SUV") (class "Default")
      (node (ref "D4") (pin "11") (pinfunction "Y4_11") (pintype "output"))
      (node (ref "INC4") (pin "1") (pinfunction "1_1") (pintype "passive"))
      (node (ref "RD40") (pin "2") (pinfunction "2_2") (pintype "passive"))
    )
    (net (code "159") (name "SUX") (class "Default")
      (node (ref "D4") (pin "15") (pinfunction "Y0_15") (pintype "output"))
      (node (ref "INC4") (pin "5") (pinfunction "5_5") (pintype "passive"))
      (node (ref "RD36") (pin "2") (pinfunction "2_2") (pintype "passive"))
    )
    (net (code "160") (name "SUY") (class "Default")
      (node (ref "D4") (pin "14") (pinfunction "Y1_14") (pintype "output"))
      (node (ref "INC4") (pin "4") (pinfunction "4_4") (pintype "passive"))
      (node (ref "RD37") (pin "2") (pinfunction "2_2") (pintype "passive"))
    )
    (net (code "161") (name "VCC") (class "Default")
      (node (ref "C1") (pin "+") (pinfunction "+_+") (pintype "passive"))
      (node (ref "C10") (pin "+") (pinfunction "+_+") (pintype "passive"))
      (node (ref "C11") (pin "+") (pinfunction "+_+") (pintype "passive"))
      (node (ref "C2") (pin "+") (pinfunction "+_+") (pintype "passive"))
      (node (ref "C3") (pin "+") (pinfunction "+_+") (pintype "passive"))
      (node (ref "C4") (pin "+") (pinfunction "+_+") (pintype "passive"))
      (node (ref "C5") (pin "+") (pinfunction "+_+") (pintype "passive"))
      (node (ref "C6") (pin "+") (pinfunction "+_+") (pintype "passive"))
      (node (ref "C7") (pin "+") (pinfunction "+_+") (pintype "passive"))
      (node (ref "C8") (pin "+") (pinfunction "+_+") (pintype "passive"))
      (node (ref "C9") (pin "+") (pinfunction "+_+") (pintype "passive"))
      (node (ref "D0") (pin "16") (pinfunction "+UB_16") (pintype "power_in"))
      (node (ref "D0") (pin "6") (pinfunction "G1_6") (pintype "input"))
      (node (ref "D1") (pin "16") (pinfunction "+UB_16") (pintype "power_in"))
      (node (ref "D1") (pin "6") (pinfunction "G1_6") (pintype "input"))
      (node (ref "D2") (pin "16") (pinfunction "+UB_16") (pintype "power_in"))
      (node (ref "D2") (pin "6") (pinfunction "G1_6") (pintype "input"))
      (node (ref "D3") (pin "16") (pinfunction "+UB_16") (pintype "power_in"))
      (node (ref "D3") (pin "6") (pinfunction "G1_6") (pintype "input"))
      (node (ref "D4") (pin "16") (pinfunction "+UB_16") (pintype "power_in"))
      (node (ref "D4") (pin "6") (pinfunction "G1_6") (pintype "input"))
      (node (ref "D5") (pin "16") (pinfunction "+UB_16") (pintype "power_in"))
      (node (ref "D5") (pin "6") (pinfunction "G1_6") (pintype "input"))
      (node (ref "D6") (pin "16") (pinfunction "+UB_16") (pintype "power_in"))
      (node (ref "D6") (pin "6") (pinfunction "G1_6") (pintype "input"))
      (node (ref "D7") (pin "16") (pinfunction "+UB_16") (pintype "power_in"))
      (node (ref "D7") (pin "6") (pinfunction "G1_6") (pintype "input"))
      (node (ref "D8") (pin "16") (pinfunction "+UB_16") (pintype "power_in"))
      (node (ref "D8") (pin "6") (pinfunction "G1_6") (pintype "input"))
      (node (ref "IR") (pin "1") (pinfunction "~{CLR}_1") (pintype "input"))
      (node (ref "IR") (pin "20") (pinfunction "+UB_20") (pintype "power_in"))
      (node (ref "PS") (pin "2") (pinfunction "2_2") (pintype "passive"))
      (node (ref "SELECTOR") (pin "16") (pinfunction "+UB_16") (pintype "power_in"))
      (node (ref "SELECTOR") (pin "6") (pinfunction "G1_6") (pintype "input"))
    )
    (net (code "162") (name "XOA") (class "Default")
      (node (ref "D8") (pin "13") (pinfunction "Y2_13") (pintype "output"))
      (node (ref "INC8") (pin "6") (pinfunction "6_6") (pintype "passive"))
      (node (ref "RD63") (pin "2") (pinfunction "2_2") (pintype "passive"))
    )
    (net (code "163") (name "XOV") (class "Default")
      (node (ref "D8") (pin "12") (pinfunction "Y3_12") (pintype "output"))
      (node (ref "INC8") (pin "5") (pinfunction "5_5") (pintype "passive"))
      (node (ref "RD64") (pin "2") (pinfunction "2_2") (pintype "passive"))
    )
    (net (code "164") (name "XOX") (class "Default")
      (node (ref "D8") (pin "15") (pinfunction "Y0_15") (pintype "output"))
      (node (ref "INC8") (pin "8") (pinfunction "8_8") (pintype "passive"))
      (node (ref "RD61") (pin "2") (pinfunction "2_2") (pintype "passive"))
    )
    (net (code "165") (name "XOY") (class "Default")
      (node (ref "D8") (pin "14") (pinfunction "Y1_14") (pintype "output"))
      (node (ref "INC8") (pin "7") (pinfunction "7_7") (pintype "passive"))
      (node (ref "RD62") (pin "2") (pinfunction "2_2") (pintype "passive"))
    )
    (net (code "166") (name "unconnected-(D0C-Y7-Pad7)") (class "Default")
      (node (ref "D0") (pin "7") (pinfunction "Y7_7") (pintype "output"))
    )
    (net (code "167") (name "unconnected-(D3C-Y5-Pad10)") (class "Default")
      (node (ref "D3") (pin "10") (pinfunction "Y5_10") (pintype "output"))
    )
    (net (code "168") (name "unconnected-(D3C-Y6-Pad9)") (class "Default")
      (node (ref "D3") (pin "9") (pinfunction "Y6_9") (pintype "output"))
    )
    (net (code "169") (name "unconnected-(D3C-Y7-Pad7)") (class "Default")
      (node (ref "D3") (pin "7") (pinfunction "Y7_7") (pintype "output"))
    )
    (net (code "170") (name "unconnected-(D4C-Y5-Pad10)") (class "Default")
      (node (ref "D4") (pin "10") (pinfunction "Y5_10") (pintype "output"))
    )
    (net (code "171") (name "unconnected-(D4C-Y6-Pad9)") (class "Default")
      (node (ref "D4") (pin "9") (pinfunction "Y6_9") (pintype "output"))
    )
    (net (code "172") (name "unconnected-(D4C-Y7-Pad7)") (class "Default")
      (node (ref "D4") (pin "7") (pinfunction "Y7_7") (pintype "output"))
    )
    (net (code "173") (name "unconnected-(D5C-Y6-Pad9)") (class "Default")
      (node (ref "D5") (pin "9") (pinfunction "Y6_9") (pintype "output"))
    )
    (net (code "174") (name "unconnected-(D5C-Y7-Pad7)") (class "Default")
      (node (ref "D5") (pin "7") (pinfunction "Y7_7") (pintype "output"))
    )
    (net (code "175") (name "unconnected-(D6C-Y6-Pad9)") (class "Default")
      (node (ref "D6") (pin "9") (pinfunction "Y6_9") (pintype "output"))
    )
    (net (code "176") (name "unconnected-(D6C-Y7-Pad7)") (class "Default")
      (node (ref "D6") (pin "7") (pinfunction "Y7_7") (pintype "output"))
    )
  )
)
